# cdu.net
KiCad netlist of a schematic drawn in EAGLE
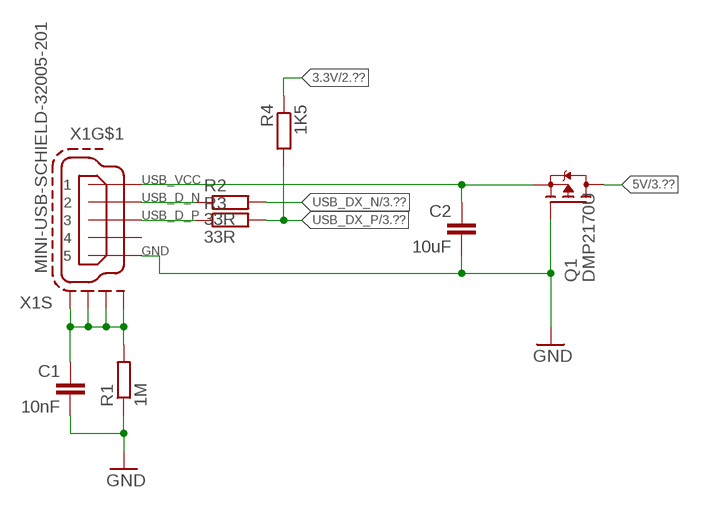
[diagram p0: schematic, sheet 1]
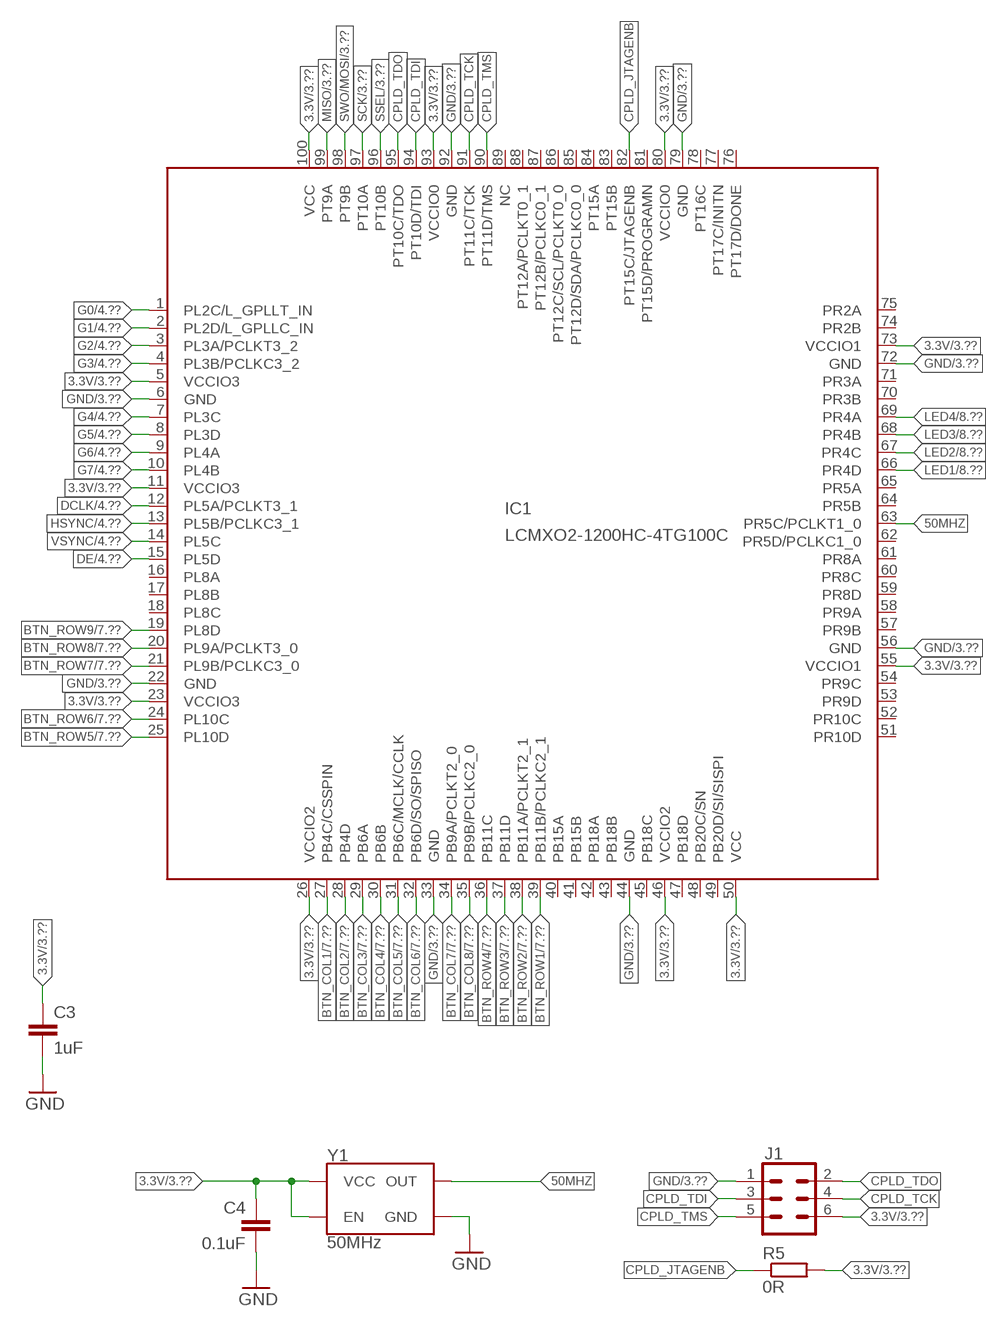
[diagram p1: schematic, sheet 2]
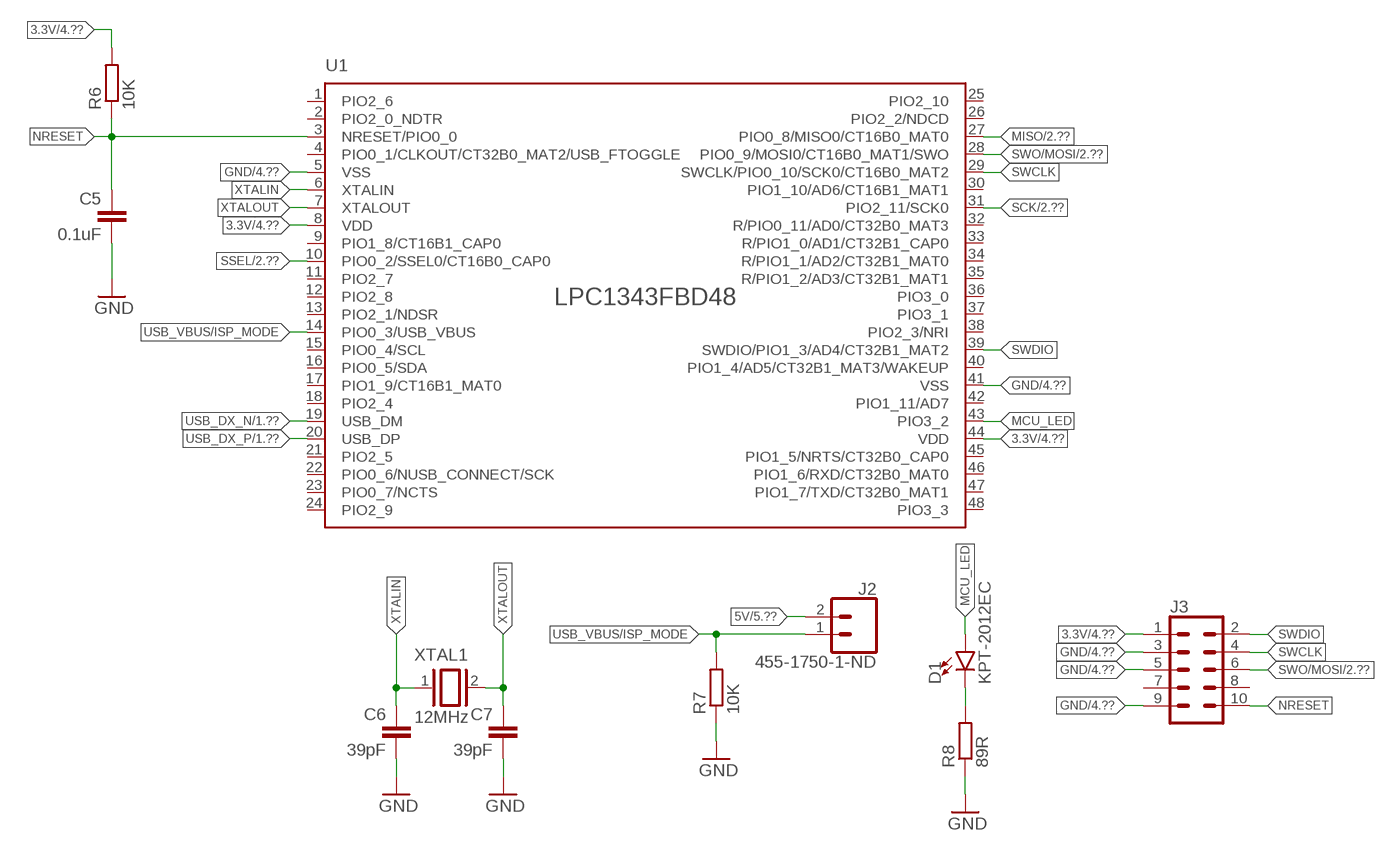
[diagram p2: schematic, sheet 3]
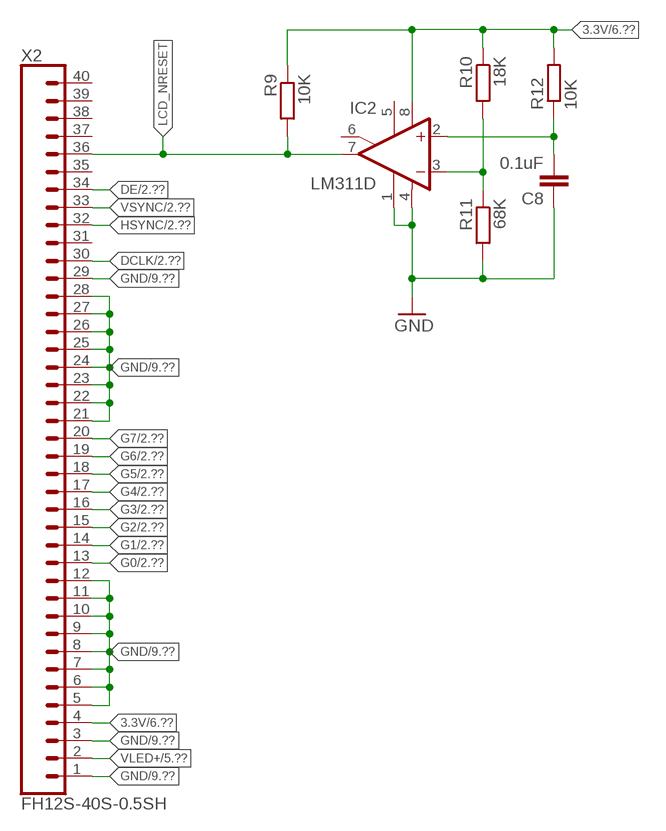
[diagram p3: schematic, sheet 4]
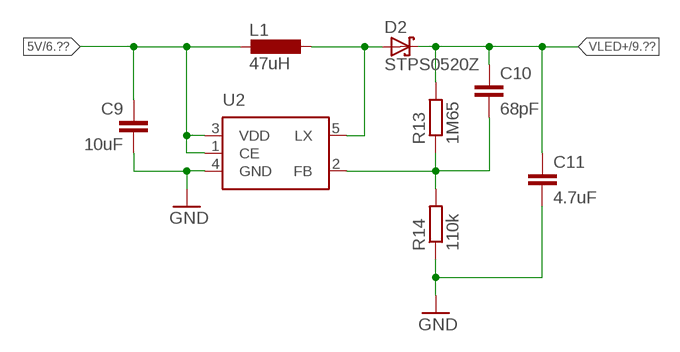
[diagram p4: schematic, sheet 5]
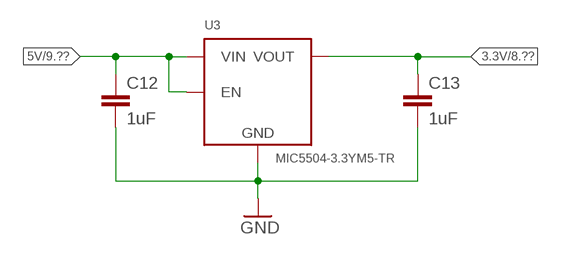
[diagram p5: schematic, sheet 6]
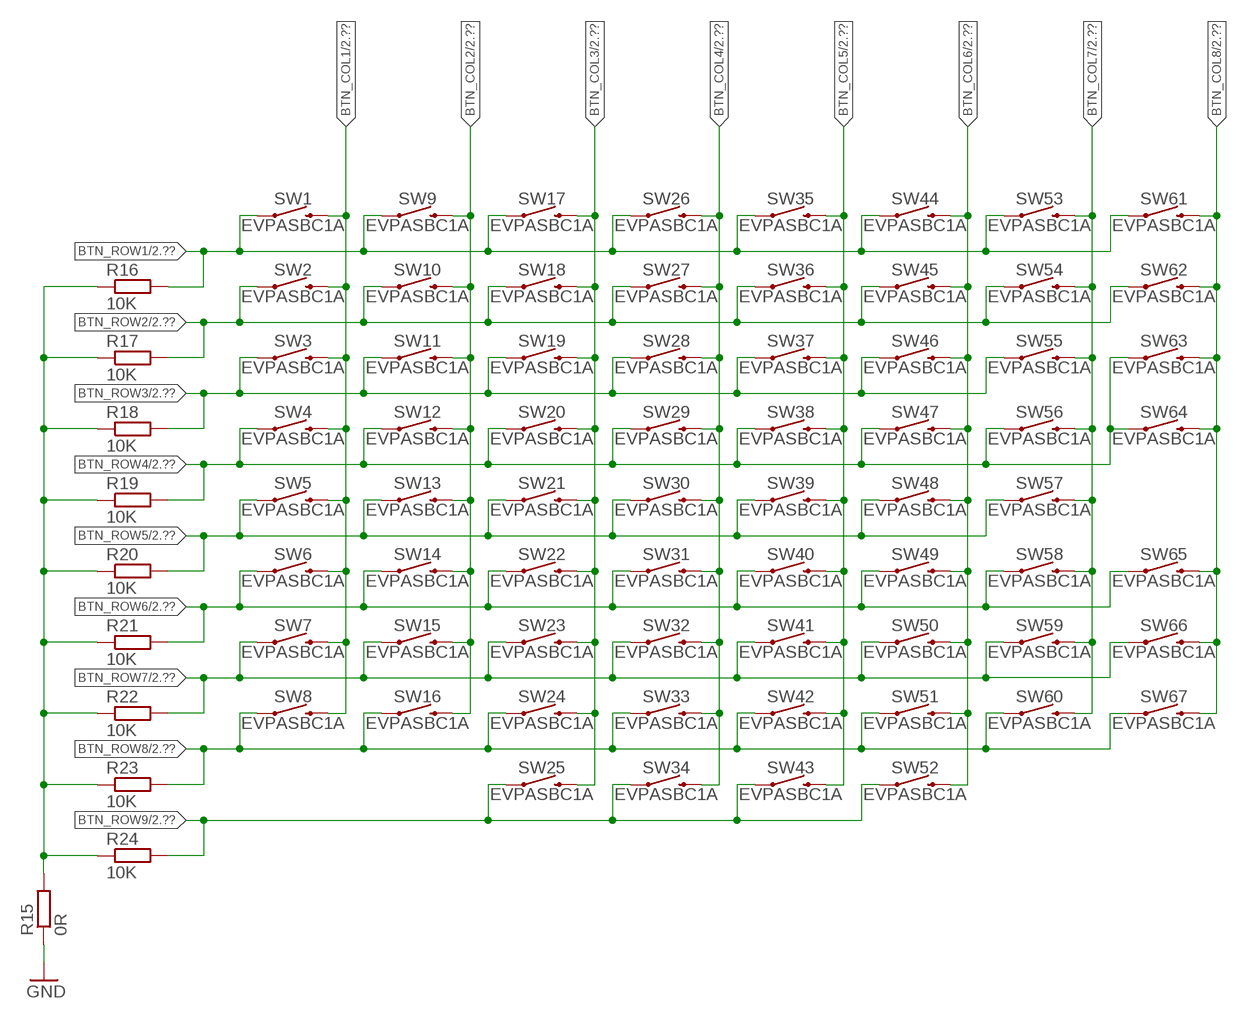
[diagram p6: schematic, sheet 7]
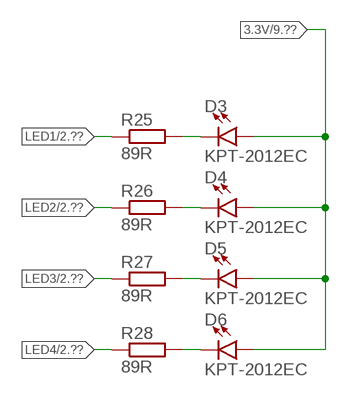
[diagram p7: schematic, sheet 8]
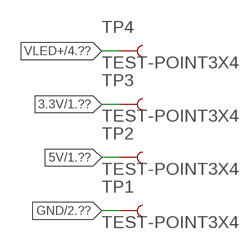
[diagram p8: schematic, sheet 9]

(export (version "E")
  (design (tool "Eeschema 10.0.6"))
  (components
    (comp (ref "TP1")
      (value "TEST-POINT3X4")
      (footprint "eagle-import:PAD.03X.04")
      (libsource (lib "eagle-import") (part "TEST-POINT3X4"))
    )
    (comp (ref "TP2")
      (value "TEST-POINT3X4")
      (footprint "eagle-import:PAD.03X.04")
      (libsource (lib "eagle-import") (part "TEST-POINT3X4"))
    )
    (comp (ref "TP3")
      (value "TEST-POINT3X4")
      (footprint "eagle-import:PAD.03X.04")
      (libsource (lib "eagle-import") (part "TEST-POINT3X4"))
    )
    (comp (ref "TP4")
      (value "TEST-POINT3X4")
      (footprint "eagle-import:PAD.03X.04")
      (libsource (lib "eagle-import") (part "TEST-POINT3X4"))
    )
    (comp (ref "C3")
      (value "1uF")
      (footprint "eagle-import:C0603")
      (libsource (lib "eagle-import") (part "resistor_348_C-EUC0603"))
    )
    (comp (ref "C4")
      (value "0.1uF")
      (footprint "eagle-import:C0603")
      (libsource (lib "eagle-import") (part "resistor_348_C-EUC0603"))
    )
    (comp (ref "IC1")
      (value "LCMXO2-1200HC-4TG100C")
      (footprint "eagle-import:TQFP100")
      (libsource (lib "eagle-import") (part "LCMXO2-1200HC-4TG100C"))
    )
    (comp (ref "J1")
      (value "CONN_03X2FEMALE_SMD")
      (footprint "eagle-import:2X3_SMD")
      (libsource (lib "eagle-import") (part "CONN_03X2FEMALE_SMD"))
    )
    (comp (ref "R5")
      (value "0R")
      (footprint "eagle-import:R0603")
      (libsource (lib "eagle-import") (part "resistor_348_R-EU_R0603"))
    )
    (comp (ref "Y1")
      (value "50MHz")
      (footprint "eagle-import:CFPS-73")
      (libsource (lib "eagle-import") (part "LFSPXO019987"))
    )
    (comp (ref "C5")
      (value "0.1uF")
      (footprint "eagle-import:C0603")
      (libsource (lib "eagle-import") (part "resistor_348_C-EUC0603"))
    )
    (comp (ref "C6")
      (value "39pF")
      (footprint "eagle-import:C0603")
      (libsource (lib "eagle-import") (part "resistor_348_C-EUC0603"))
    )
    (comp (ref "C7")
      (value "39pF")
      (footprint "eagle-import:C0603")
      (libsource (lib "eagle-import") (part "resistor_348_C-EUC0603"))
    )
    (comp (ref "D1")
      (value "KPT-2012EC")
      (footprint "eagle-import:KPT-2012EC")
      (libsource (lib "eagle-import") (part "KPT-2012EC"))
    )
    (comp (ref "J2")
      (value "455-1750-1-ND")
      (footprint "eagle-import:1X02_SMD")
      (libsource (lib "eagle-import") (part "CONN_02SMD"))
    )
    (comp (ref "J3")
      (value "CONN_05X2SMD_12.7")
      (footprint "eagle-import:2X5_SMD_1.27MM")
      (libsource (lib "eagle-import") (part "CONN_05X2SMD_12.7"))
    )
    (comp (ref "R6")
      (value "10K")
      (footprint "eagle-import:R0603")
      (libsource (lib "eagle-import") (part "resistor_348_R-EU_R0603"))
    )
    (comp (ref "R7")
      (value "10K")
      (footprint "eagle-import:R0603")
      (libsource (lib "eagle-import") (part "resistor_348_R-EU_R0603"))
    )
    (comp (ref "R8")
      (value "89R")
      (footprint "eagle-import:R0603")
      (libsource (lib "eagle-import") (part "resistor_348_R-EU_R0603"))
    )
    (comp (ref "U1")
      (value "LPC1343FBD48")
      (footprint "eagle-import:LQFP-48")
      (libsource (lib "eagle-import") (part "LPC1343FBD48"))
    )
    (comp (ref "XTAL1")
      (value "12MHz")
      (footprint "eagle-import:CAA-12.000-18-3050-X")
      (libsource (lib "eagle-import") (part "CRYSTAL"))
    )
    (comp (ref "C9")
      (value "10uF")
      (footprint "eagle-import:C0805K")
      (libsource (lib "eagle-import") (part "resistor_348_C-EUC0805K"))
    )
    (comp (ref "C10")
      (value "68pF")
      (footprint "eagle-import:C0603")
      (libsource (lib "eagle-import") (part "resistor_348_C-EUC0603"))
    )
    (comp (ref "C11")
      (value "4.7uF")
      (footprint "eagle-import:C0603")
      (libsource (lib "eagle-import") (part "resistor_348_C-EUC0603"))
    )
    (comp (ref "D2")
      (value "STPS0520Z")
      (footprint "eagle-import:SOD123")
      (libsource (lib "eagle-import") (part "STPS0520Z"))
    )
    (comp (ref "L1")
      (value "47uH")
      (footprint "eagle-import:TYS4018470M-10")
      (libsource (lib "eagle-import") (part "TYS4018470M-10"))
    )
    (comp (ref "R13")
      (value "1M65")
      (footprint "eagle-import:R0603")
      (libsource (lib "eagle-import") (part "resistor_348_R-EU_R0603"))
    )
    (comp (ref "R14")
      (value "110k")
      (footprint "eagle-import:R0603")
      (libsource (lib "eagle-import") (part "resistor_348_R-EU_R0603"))
    )
    (comp (ref "U2")
      (value "NCP1406")
      (footprint "eagle-import:TSOP-5")
      (libsource (lib "eagle-import") (part "NCP1406"))
    )
    (comp (ref "C1")
      (value "10nF")
      (footprint "eagle-import:C0603")
      (libsource (lib "eagle-import") (part "resistor_348_C-EUC0603"))
    )
    (comp (ref "C2")
      (value "10uF")
      (footprint "eagle-import:C0805K")
      (libsource (lib "eagle-import") (part "resistor_348_C-EUC0805K"))
    )
    (comp (ref "Q1")
      (value "DMP2170U")
      (footprint "eagle-import:SOT23")
      (libsource (lib "eagle-import") (part "DMP2170U"))
    )
    (comp (ref "R1")
      (value "1M")
      (footprint "eagle-import:R0603")
      (libsource (lib "eagle-import") (part "resistor_348_R-EU_R0603"))
    )
    (comp (ref "R2")
      (value "33R")
      (footprint "eagle-import:R0603")
      (libsource (lib "eagle-import") (part "resistor_348_R-EU_R0603"))
    )
    (comp (ref "R3")
      (value "33R")
      (footprint "eagle-import:R0603")
      (libsource (lib "eagle-import") (part "resistor_348_R-EU_R0603"))
    )
    (comp (ref "R4")
      (value "1K5")
      (footprint "eagle-import:R0603")
      (libsource (lib "eagle-import") (part "resistor_348_R-EU_R0603"))
    )
    (comp (ref "X1")
      (value "MINI-USB-SCHIELD-32005-201")
      (footprint "eagle-import:32005-201")
      (libsource (lib "eagle-import") (part "MINI-USB-SCHIELD-32005-201"))
    )
    (comp (ref "C8")
      (value "0.1uF")
      (footprint "eagle-import:C0603")
      (libsource (lib "eagle-import") (part "C-EUC0603"))
    )
    (comp (ref "IC2")
      (value "LM311D")
      (footprint "eagle-import:SO08")
      (libsource (lib "eagle-import") (part "LM311D"))
    )
    (comp (ref "R9")
      (value "10K")
      (footprint "eagle-import:R0603")
      (libsource (lib "eagle-import") (part "R-EU_R0603"))
    )
    (comp (ref "R10")
      (value "18K")
      (footprint "eagle-import:R0603")
      (libsource (lib "eagle-import") (part "R-EU_R0603"))
    )
    (comp (ref "R11")
      (value "68K")
      (footprint "eagle-import:R0603")
      (libsource (lib "eagle-import") (part "R-EU_R0603"))
    )
    (comp (ref "R12")
      (value "10K")
      (footprint "eagle-import:R0603")
      (libsource (lib "eagle-import") (part "R-EU_R0603"))
    )
    (comp (ref "X2")
      (value "FH12S-40S-0.5SH")
      (footprint "eagle-import:FH12S-40S-0.5SH")
      (libsource (lib "eagle-import") (part "FH12S-40S-0.5SH"))
    )
    (comp (ref "D3")
      (value "KPT-2012EC")
      (footprint "eagle-import:KPT-2012EC")
      (libsource (lib "eagle-import") (part "KPT-2012EC"))
    )
    (comp (ref "D4")
      (value "KPT-2012EC")
      (footprint "eagle-import:KPT-2012EC")
      (libsource (lib "eagle-import") (part "KPT-2012EC"))
    )
    (comp (ref "D5")
      (value "KPT-2012EC")
      (footprint "eagle-import:KPT-2012EC")
      (libsource (lib "eagle-import") (part "KPT-2012EC"))
    )
    (comp (ref "D6")
      (value "KPT-2012EC")
      (footprint "eagle-import:KPT-2012EC")
      (libsource (lib "eagle-import") (part "KPT-2012EC"))
    )
    (comp (ref "R25")
      (value "89R")
      (footprint "eagle-import:R0603")
      (libsource (lib "eagle-import") (part "resistor_348_R-EU_R0603"))
    )
    (comp (ref "R26")
      (value "89R")
      (footprint "eagle-import:R0603")
      (libsource (lib "eagle-import") (part "resistor_348_R-EU_R0603"))
    )
    (comp (ref "R27")
      (value "89R")
      (footprint "eagle-import:R0603")
      (libsource (lib "eagle-import") (part "resistor_348_R-EU_R0603"))
    )
    (comp (ref "R28")
      (value "89R")
      (footprint "eagle-import:R0603")
      (libsource (lib "eagle-import") (part "resistor_348_R-EU_R0603"))
    )
    (comp (ref "R15")
      (value "0R")
      (footprint "eagle-import:R0603")
      (libsource (lib "eagle-import") (part "resistor_348_R-EU_R0603"))
    )
    (comp (ref "R16")
      (value "10K")
      (footprint "eagle-import:R0603")
      (libsource (lib "eagle-import") (part "resistor_348_R-EU_R0603"))
    )
    (comp (ref "R17")
      (value "10K")
      (footprint "eagle-import:R0603")
      (libsource (lib "eagle-import") (part "resistor_348_R-EU_R0603"))
    )
    (comp (ref "R18")
      (value "10K")
      (footprint "eagle-import:R0603")
      (libsource (lib "eagle-import") (part "resistor_348_R-EU_R0603"))
    )
    (comp (ref "R19")
      (value "10K")
      (footprint "eagle-import:R0603")
      (libsource (lib "eagle-import") (part "resistor_348_R-EU_R0603"))
    )
    (comp (ref "R20")
      (value "10K")
      (footprint "eagle-import:R0603")
      (libsource (lib "eagle-import") (part "resistor_348_R-EU_R0603"))
    )
    (comp (ref "R21")
      (value "10K")
      (footprint "eagle-import:R0603")
      (libsource (lib "eagle-import") (part "resistor_348_R-EU_R0603"))
    )
    (comp (ref "R22")
      (value "10K")
      (footprint "eagle-import:R0603")
      (libsource (lib "eagle-import") (part "resistor_348_R-EU_R0603"))
    )
    (comp (ref "R23")
      (value "10K")
      (footprint "eagle-import:R0603")
      (libsource (lib "eagle-import") (part "resistor_348_R-EU_R0603"))
    )
    (comp (ref "R24")
      (value "10K")
      (footprint "eagle-import:R0603")
      (libsource (lib "eagle-import") (part "resistor_348_R-EU_R0603"))
    )
    (comp (ref "SW1")
      (value "EVPASBC1A")
      (footprint "eagle-import:EVPASBC1A")
      (libsource (lib "eagle-import") (part "EVPASBC1A"))
    )
    (comp (ref "SW2")
      (value "EVPASBC1A")
      (footprint "eagle-import:EVPASBC1A")
      (libsource (lib "eagle-import") (part "EVPASBC1A"))
    )
    (comp (ref "SW3")
      (value "EVPASBC1A")
      (footprint "eagle-import:EVPASBC1A")
      (libsource (lib "eagle-import") (part "EVPASBC1A"))
    )
    (comp (ref "SW4")
      (value "EVPASBC1A")
      (footprint "eagle-import:EVPASBC1A")
      (libsource (lib "eagle-import") (part "EVPASBC1A"))
    )
    (comp (ref "SW5")
      (value "EVPASBC1A")
      (footprint "eagle-import:EVPASBC1A")
      (libsource (lib "eagle-import") (part "EVPASBC1A"))
    )
    (comp (ref "SW6")
      (value "EVPASBC1A")
      (footprint "eagle-import:EVPASBC1A")
      (libsource (lib "eagle-import") (part "EVPASBC1A"))
    )
    (comp (ref "SW7")
      (value "EVPASBC1A")
      (footprint "eagle-import:EVPASBC1A")
      (libsource (lib "eagle-import") (part "EVPASBC1A"))
    )
    (comp (ref "SW8")
      (value "EVPASBC1A")
      (footprint "eagle-import:EVPASBC1A")
      (libsource (lib "eagle-import") (part "EVPASBC1A"))
    )
    (comp (ref "SW9")
      (value "EVPASBC1A")
      (footprint "eagle-import:EVPASBC1A")
      (libsource (lib "eagle-import") (part "EVPASBC1A"))
    )
    (comp (ref "SW10")
      (value "EVPASBC1A")
      (footprint "eagle-import:EVPASBC1A")
      (libsource (lib "eagle-import") (part "EVPASBC1A"))
    )
    (comp (ref "SW11")
      (value "EVPASBC1A")
      (footprint "eagle-import:EVPASBC1A")
      (libsource (lib "eagle-import") (part "EVPASBC1A"))
    )
    (comp (ref "SW12")
      (value "EVPASBC1A")
      (footprint "eagle-import:EVPASBC1A")
      (libsource (lib "eagle-import") (part "EVPASBC1A"))
    )
    (comp (ref "SW13")
      (value "EVPASBC1A")
      (footprint "eagle-import:EVPASBC1A")
      (libsource (lib "eagle-import") (part "EVPASBC1A"))
    )
    (comp (ref "SW14")
      (value "EVPASBC1A")
      (footprint "eagle-import:EVPASBC1A")
      (libsource (lib "eagle-import") (part "EVPASBC1A"))
    )
    (comp (ref "SW15")
      (value "EVPASBC1A")
      (footprint "eagle-import:EVPASBC1A")
      (libsource (lib "eagle-import") (part "EVPASBC1A"))
    )
    (comp (ref "SW16")
      (value "EVPASBC1A")
      (footprint "eagle-import:EVPASBC1A")
      (libsource (lib "eagle-import") (part "EVPASBC1A"))
    )
    (comp (ref "SW17")
      (value "EVPASBC1A")
      (footprint "eagle-import:EVPASBC1A")
      (libsource (lib "eagle-import") (part "EVPASBC1A"))
    )
    (comp (ref "SW18")
      (value "EVPASBC1A")
      (footprint "eagle-import:EVPASBC1A")
      (libsource (lib "eagle-import") (part "EVPASBC1A"))
    )
    (comp (ref "SW19")
      (value "EVPASBC1A")
      (footprint "eagle-import:EVPASBC1A")
      (libsource (lib "eagle-import") (part "EVPASBC1A"))
    )
    (comp (ref "SW20")
      (value "EVPASBC1A")
      (footprint "eagle-import:EVPASBC1A")
      (libsource (lib "eagle-import") (part "EVPASBC1A"))
    )
    (comp (ref "SW21")
      (value "EVPASBC1A")
      (footprint "eagle-import:EVPASBC1A")
      (libsource (lib "eagle-import") (part "EVPASBC1A"))
    )
    (comp (ref "SW22")
      (value "EVPASBC1A")
      (footprint "eagle-import:EVPASBC1A")
      (libsource (lib "eagle-import") (part "EVPASBC1A"))
    )
    (comp (ref "SW23")
      (value "EVPASBC1A")
      (footprint "eagle-import:EVPASBC1A")
      (libsource (lib "eagle-import") (part "EVPASBC1A"))
    )
    (comp (ref "SW24")
      (value "EVPASBC1A")
      (footprint "eagle-import:EVPASBC1A")
      (libsource (lib "eagle-import") (part "EVPASBC1A"))
    )
    (comp (ref "SW25")
      (value "EVPASBC1A")
      (footprint "eagle-import:EVPASBC1A")
      (libsource (lib "eagle-import") (part "EVPASBC1A"))
    )
    (comp (ref "SW26")
      (value "EVPASBC1A")
      (footprint "eagle-import:EVPASBC1A")
      (libsource (lib "eagle-import") (part "EVPASBC1A"))
    )
    (comp (ref "SW27")
      (value "EVPASBC1A")
      (footprint "eagle-import:EVPASBC1A")
      (libsource (lib "eagle-import") (part "EVPASBC1A"))
    )
    (comp (ref "SW28")
      (value "EVPASBC1A")
      (footprint "eagle-import:EVPASBC1A")
      (libsource (lib "eagle-import") (part "EVPASBC1A"))
    )
    (comp (ref "SW29")
      (value "EVPASBC1A")
      (footprint "eagle-import:EVPASBC1A")
      (libsource (lib "eagle-import") (part "EVPASBC1A"))
    )
    (comp (ref "SW30")
      (value "EVPASBC1A")
      (footprint "eagle-import:EVPASBC1A")
      (libsource (lib "eagle-import") (part "EVPASBC1A"))
    )
    (comp (ref "SW31")
      (value "EVPASBC1A")
      (footprint "eagle-import:EVPASBC1A")
      (libsource (lib "eagle-import") (part "EVPASBC1A"))
    )
    (comp (ref "SW32")
      (value "EVPASBC1A")
      (footprint "eagle-import:EVPASBC1A")
      (libsource (lib "eagle-import") (part "EVPASBC1A"))
    )
    (comp (ref "SW33")
      (value "EVPASBC1A")
      (footprint "eagle-import:EVPASBC1A")
      (libsource (lib "eagle-import") (part "EVPASBC1A"))
    )
    (comp (ref "SW34")
      (value "EVPASBC1A")
      (footprint "eagle-import:EVPASBC1A")
      (libsource (lib "eagle-import") (part "EVPASBC1A"))
    )
    (comp (ref "SW35")
      (value "EVPASBC1A")
      (footprint "eagle-import:EVPASBC1A")
      (libsource (lib "eagle-import") (part "EVPASBC1A"))
    )
    (comp (ref "SW36")
      (value "EVPASBC1A")
      (footprint "eagle-import:EVPASBC1A")
      (libsource (lib "eagle-import") (part "EVPASBC1A"))
    )
    (comp (ref "SW37")
      (value "EVPASBC1A")
      (footprint "eagle-import:EVPASBC1A")
      (libsource (lib "eagle-import") (part "EVPASBC1A"))
    )
    (comp (ref "SW38")
      (value "EVPASBC1A")
      (footprint "eagle-import:EVPASBC1A")
      (libsource (lib "eagle-import") (part "EVPASBC1A"))
    )
    (comp (ref "SW39")
      (value "EVPASBC1A")
      (footprint "eagle-import:EVPASBC1A")
      (libsource (lib "eagle-import") (part "EVPASBC1A"))
    )
    (comp (ref "SW40")
      (value "EVPASBC1A")
      (footprint "eagle-import:EVPASBC1A")
      (libsource (lib "eagle-import") (part "EVPASBC1A"))
    )
    (comp (ref "SW41")
      (value "EVPASBC1A")
      (footprint "eagle-import:EVPASBC1A")
      (libsource (lib "eagle-import") (part "EVPASBC1A"))
    )
    (comp (ref "SW42")
      (value "EVPASBC1A")
      (footprint "eagle-import:EVPASBC1A")
      (libsource (lib "eagle-import") (part "EVPASBC1A"))
    )
    (comp (ref "SW43")
      (value "EVPASBC1A")
      (footprint "eagle-import:EVPASBC1A")
      (libsource (lib "eagle-import") (part "EVPASBC1A"))
    )
    (comp (ref "SW44")
      (value "EVPASBC1A")
      (footprint "eagle-import:EVPASBC1A")
      (libsource (lib "eagle-import") (part "EVPASBC1A"))
    )
    (comp (ref "SW45")
      (value "EVPASBC1A")
      (footprint "eagle-import:EVPASBC1A")
      (libsource (lib "eagle-import") (part "EVPASBC1A"))
    )
    (comp (ref "SW46")
      (value "EVPASBC1A")
      (footprint "eagle-import:EVPASBC1A")
      (libsource (lib "eagle-import") (part "EVPASBC1A"))
    )
    (comp (ref "SW47")
      (value "EVPASBC1A")
      (footprint "eagle-import:EVPASBC1A")
      (libsource (lib "eagle-import") (part "EVPASBC1A"))
    )
    (comp (ref "SW48")
      (value "EVPASBC1A")
      (footprint "eagle-import:EVPASBC1A")
      (libsource (lib "eagle-import") (part "EVPASBC1A"))
    )
    (comp (ref "SW49")
      (value "EVPASBC1A")
      (footprint "eagle-import:EVPASBC1A")
      (libsource (lib "eagle-import") (part "EVPASBC1A"))
    )
    (comp (ref "SW50")
      (value "EVPASBC1A")
      (footprint "eagle-import:EVPASBC1A")
      (libsource (lib "eagle-import") (part "EVPASBC1A"))
    )
    (comp (ref "SW51")
      (value "EVPASBC1A")
      (footprint "eagle-import:EVPASBC1A")
      (libsource (lib "eagle-import") (part "EVPASBC1A"))
    )
    (comp (ref "SW52")
      (value "EVPASBC1A")
      (footprint "eagle-import:EVPASBC1A")
      (libsource (lib "eagle-import") (part "EVPASBC1A"))
    )
    (comp (ref "SW53")
      (value "EVPASBC1A")
      (footprint "eagle-import:EVPASBC1A")
      (libsource (lib "eagle-import") (part "EVPASBC1A"))
    )
    (comp (ref "SW54")
      (value "EVPASBC1A")
      (footprint "eagle-import:EVPASBC1A")
      (libsource (lib "eagle-import") (part "EVPASBC1A"))
    )
    (comp (ref "SW55")
      (value "EVPASBC1A")
      (footprint "eagle-import:EVPASBC1A")
      (libsource (lib "eagle-import") (part "EVPASBC1A"))
    )
    (comp (ref "SW56")
      (value "EVPASBC1A")
      (footprint "eagle-import:EVPASBC1A")
      (libsource (lib "eagle-import") (part "EVPASBC1A"))
    )
    (comp (ref "SW57")
      (value "EVPASBC1A")
      (footprint "eagle-import:EVPASBC1A")
      (libsource (lib "eagle-import") (part "EVPASBC1A"))
    )
    (comp (ref "SW58")
      (value "EVPASBC1A")
      (footprint "eagle-import:EVPASBC1A")
      (libsource (lib "eagle-import") (part "EVPASBC1A"))
    )
    (comp (ref "SW59")
      (value "EVPASBC1A")
      (footprint "eagle-import:EVPASBC1A")
      (libsource (lib "eagle-import") (part "EVPASBC1A"))
    )
    (comp (ref "SW60")
      (value "EVPASBC1A")
      (footprint "eagle-import:EVPASBC1A")
      (libsource (lib "eagle-import") (part "EVPASBC1A"))
    )
    (comp (ref "SW61")
      (value "EVPASBC1A")
      (footprint "eagle-import:EVPASBC1A")
      (libsource (lib "eagle-import") (part "EVPASBC1A"))
    )
    (comp (ref "SW62")
      (value "EVPASBC1A")
      (footprint "eagle-import:EVPASBC1A")
      (libsource (lib "eagle-import") (part "EVPASBC1A"))
    )
    (comp (ref "SW63")
      (value "EVPASBC1A")
      (footprint "eagle-import:EVPASBC1A")
      (libsource (lib "eagle-import") (part "EVPASBC1A"))
    )
    (comp (ref "SW64")
      (value "EVPASBC1A")
      (footprint "eagle-import:EVPASBC1A")
      (libsource (lib "eagle-import") (part "EVPASBC1A"))
    )
    (comp (ref "SW65")
      (value "EVPASBC1A")
      (footprint "eagle-import:EVPASBC1A")
      (libsource (lib "eagle-import") (part "EVPASBC1A"))
    )
    (comp (ref "SW66")
      (value "EVPASBC1A")
      (footprint "eagle-import:EVPASBC1A")
      (libsource (lib "eagle-import") (part "EVPASBC1A"))
    )
    (comp (ref "SW67")
      (value "EVPASBC1A")
      (footprint "eagle-import:EVPASBC1A")
      (libsource (lib "eagle-import") (part "EVPASBC1A"))
    )
    (comp (ref "C12")
      (value "1uF")
      (footprint "eagle-import:C0603")
      (libsource (lib "eagle-import") (part "resistor_348_C-EUC0603"))
    )
    (comp (ref "C13")
      (value "1uF")
      (footprint "eagle-import:C0603")
      (libsource (lib "eagle-import") (part "resistor_348_C-EUC0603"))
    )
    (comp (ref "U3")
      (value "MIC5504-3.3YM5-TR")
      (footprint "eagle-import:SOT23-5")
      (fields (field (name "SPICEPREFIX") "E"))
      (libsource (lib "eagle-import") (part "MIC5504-TR-3.3YM5"))
    )
  )
  (nets
    (net (code "1") (name "3.3V") (class "Default")
      (node (ref "C13") (pin "1") (pinfunction "1_1") (pintype "passive"))
      (node (ref "C3") (pin "1") (pinfunction "1_1") (pintype "passive"))
      (node (ref "C4") (pin "1") (pinfunction "1_1") (pintype "passive"))
      (node (ref "D3") (pin "A") (pinfunction "A_A") (pintype "passive"))
      (node (ref "D4") (pin "A") (pinfunction "A_A") (pintype "passive"))
      (node (ref "D5") (pin "A") (pinfunction "A_A") (pintype "passive"))
      (node (ref "D6") (pin "A") (pinfunction "A_A") (pintype "passive"))
      (node (ref "IC1") (pin "100") (pinfunction "VCC_100") (pintype "power_in"))
      (node (ref "IC1") (pin "11") (pinfunction "VCCIO3_11") (pintype "power_in"))
      (node (ref "IC1") (pin "23") (pinfunction "VCCIO3_23") (pintype "power_in"))
      (node (ref "IC1") (pin "26") (pinfunction "VCCIO2_26") (pintype "power_in"))
      (node (ref "IC1") (pin "46") (pinfunction "VCCIO2_46") (pintype "power_in"))
      (node (ref "IC1") (pin "5") (pinfunction "VCCIO3_5") (pintype "power_in"))
      (node (ref "IC1") (pin "50") (pinfunction "VCC_50") (pintype "power_in"))
      (node (ref "IC1") (pin "55") (pinfunction "VCCIO1_55") (pintype "power_in"))
      (node (ref "IC1") (pin "73") (pinfunction "VCCIO1_73") (pintype "power_in"))
      (node (ref "IC1") (pin "80") (pinfunction "VCCIO0_80") (pintype "power_in"))
      (node (ref "IC1") (pin "93") (pinfunction "VCCIO0_93") (pintype "power_in"))
      (node (ref "IC2") (pin "8") (pinfunction "V+_8") (pintype "power_in"))
      (node (ref "J1") (pin "6") (pinfunction "6_6") (pintype "bidirectional"))
      (node (ref "J3") (pin "1") (pinfunction "1_1") (pintype "passive"))
      (node (ref "R10") (pin "1") (pinfunction "1_1") (pintype "passive"))
      (node (ref "R12") (pin "2") (pinfunction "2_2") (pintype "passive"))
      (node (ref "R4") (pin "1") (pinfunction "1_1") (pintype "passive"))
      (node (ref "R5") (pin "2") (pinfunction "2_2") (pintype "passive"))
      (node (ref "R6") (pin "2") (pinfunction "2_2") (pintype "passive"))
      (node (ref "R9") (pin "1") (pinfunction "1_1") (pintype "passive"))
      (node (ref "TP3") (pin "P$1") (pinfunction "1_P$1") (pintype "bidirectional"))
      (node (ref "U1") (pin "44") (pinfunction "VDD_44") (pintype "bidirectional"))
      (node (ref "U1") (pin "8") (pinfunction "VDD_8") (pintype "bidirectional"))
      (node (ref "U3") (pin "5") (pinfunction "VOUT_5") (pintype "power_in"))
      (node (ref "X2") (pin "4") (pinfunction "4_4") (pintype "passive"))
      (node (ref "Y1") (pin "1") (pinfunction "EN_1") (pintype "bidirectional"))
      (node (ref "Y1") (pin "4") (pinfunction "VCC_4") (pintype "bidirectional"))
    )
    (net (code "2") (name "5V") (class "Default")
      (node (ref "C12") (pin "1") (pinfunction "1_1") (pintype "passive"))
      (node (ref "C9") (pin "1") (pinfunction "1_1") (pintype "passive"))
      (node (ref "J2") (pin "2") (pinfunction "2_2") (pintype "passive"))
      (node (ref "L1") (pin "2") (pinfunction "2_2") (pintype "passive"))
      (node (ref "Q1") (pin "3") (pinfunction "D_3") (pintype "passive"))
      (node (ref "TP2") (pin "P$1") (pinfunction "1_P$1") (pintype "bidirectional"))
      (node (ref "U2") (pin "1") (pinfunction "CE_1") (pintype "bidirectional"))
      (node (ref "U2") (pin "3") (pinfunction "VDD_3") (pintype "bidirectional"))
      (node (ref "U3") (pin "1") (pinfunction "VIN_1") (pintype "power_in"))
      (node (ref "U3") (pin "3") (pinfunction "EN_3") (pintype "input"))
    )
    (net (code "3") (name "50MHZ") (class "Default")
      (node (ref "IC1") (pin "63") (pinfunction "PR5C/PCLKT1_0_63") (pintype "bidirectional"))
      (node (ref "Y1") (pin "3") (pinfunction "OUT_3") (pintype "bidirectional"))
    )
    (net (code "4") (name "BTN_COL1") (class "Default")
      (node (ref "IC1") (pin "27") (pinfunction "PB4C/CSSPIN_27") (pintype "bidirectional"))
      (node (ref "SW1") (pin "P$2") (pinfunction "2_P$2") (pintype "passive"))
      (node (ref "SW2") (pin "P$2") (pinfunction "2_P$2") (pintype "passive"))
      (node (ref "SW3") (pin "P$2") (pinfunction "2_P$2") (pintype "passive"))
      (node (ref "SW4") (pin "P$2") (pinfunction "2_P$2") (pintype "passive"))
      (node (ref "SW5") (pin "P$2") (pinfunction "2_P$2") (pintype "passive"))
      (node (ref "SW6") (pin "P$2") (pinfunction "2_P$2") (pintype "passive"))
      (node (ref "SW7") (pin "P$2") (pinfunction "2_P$2") (pintype "passive"))
      (node (ref "SW8") (pin "P$2") (pinfunction "2_P$2") (pintype "passive"))
    )
    (net (code "5") (name "BTN_COL2") (class "Default")
      (node (ref "IC1") (pin "28") (pinfunction "PB4D_28") (pintype "bidirectional"))
      (node (ref "SW10") (pin "P$2") (pinfunction "2_P$2") (pintype "passive"))
      (node (ref "SW11") (pin "P$2") (pinfunction "2_P$2") (pintype "passive"))
      (node (ref "SW12") (pin "P$2") (pinfunction "2_P$2") (pintype "passive"))
      (node (ref "SW13") (pin "P$2") (pinfunction "2_P$2") (pintype "passive"))
      (node (ref "SW14") (pin "P$2") (pinfunction "2_P$2") (pintype "passive"))
      (node (ref "SW15") (pin "P$2") (pinfunction "2_P$2") (pintype "passive"))
      (node (ref "SW16") (pin "P$2") (pinfunction "2_P$2") (pintype "passive"))
      (node (ref "SW9") (pin "P$2") (pinfunction "2_P$2") (pintype "passive"))
    )
    (net (code "6") (name "BTN_COL3") (class "Default")
      (node (ref "IC1") (pin "29") (pinfunction "PB6A_29") (pintype "bidirectional"))
      (node (ref "SW17") (pin "P$2") (pinfunction "2_P$2") (pintype "passive"))
      (node (ref "SW18") (pin "P$2") (pinfunction "2_P$2") (pintype "passive"))
      (node (ref "SW19") (pin "P$2") (pinfunction "2_P$2") (pintype "passive"))
      (node (ref "SW20") (pin "P$2") (pinfunction "2_P$2") (pintype "passive"))
      (node (ref "SW21") (pin "P$2") (pinfunction "2_P$2") (pintype "passive"))
      (node (ref "SW22") (pin "P$2") (pinfunction "2_P$2") (pintype "passive"))
      (node (ref "SW23") (pin "P$2") (pinfunction "2_P$2") (pintype "passive"))
      (node (ref "SW24") (pin "P$2") (pinfunction "2_P$2") (pintype "passive"))
      (node (ref "SW25") (pin "P$2") (pinfunction "2_P$2") (pintype "passive"))
    )
    (net (code "7") (name "BTN_COL4") (class "Default")
      (node (ref "IC1") (pin "30") (pinfunction "PB6B_30") (pintype "bidirectional"))
      (node (ref "SW26") (pin "P$2") (pinfunction "2_P$2") (pintype "passive"))
      (node (ref "SW27") (pin "P$2") (pinfunction "2_P$2") (pintype "passive"))
      (node (ref "SW28") (pin "P$2") (pinfunction "2_P$2") (pintype "passive"))
      (node (ref "SW29") (pin "P$2") (pinfunction "2_P$2") (pintype "passive"))
      (node (ref "SW30") (pin "P$2") (pinfunction "2_P$2") (pintype "passive"))
      (node (ref "SW31") (pin "P$2") (pinfunction "2_P$2") (pintype "passive"))
      (node (ref "SW32") (pin "P$2") (pinfunction "2_P$2") (pintype "passive"))
      (node (ref "SW33") (pin "P$2") (pinfunction "2_P$2") (pintype "passive"))
      (node (ref "SW34") (pin "P$2") (pinfunction "2_P$2") (pintype "passive"))
    )
    (net (code "8") (name "BTN_COL5") (class "Default")
      (node (ref "IC1") (pin "31") (pinfunction "PB6C/MCLK/CCLK_31") (pintype "bidirectional"))
      (node (ref "SW35") (pin "P$2") (pinfunction "2_P$2") (pintype "passive"))
      (node (ref "SW36") (pin "P$2") (pinfunction "2_P$2") (pintype "passive"))
      (node (ref "SW37") (pin "P$2") (pinfunction "2_P$2") (pintype "passive"))
      (node (ref "SW38") (pin "P$2") (pinfunction "2_P$2") (pintype "passive"))
      (node (ref "SW39") (pin "P$2") (pinfunction "2_P$2") (pintype "passive"))
      (node (ref "SW40") (pin "P$2") (pinfunction "2_P$2") (pintype "passive"))
      (node (ref "SW41") (pin "P$2") (pinfunction "2_P$2") (pintype "passive"))
      (node (ref "SW42") (pin "P$2") (pinfunction "2_P$2") (pintype "passive"))
      (node (ref "SW43") (pin "P$2") (pinfunction "2_P$2") (pintype "passive"))
    )
    (net (code "9") (name "BTN_COL6") (class "Default")
      (node (ref "IC1") (pin "32") (pinfunction "PB6D/SO/SPISO_32") (pintype "bidirectional"))
      (node (ref "SW44") (pin "P$2") (pinfunction "2_P$2") (pintype "passive"))
      (node (ref "SW45") (pin "P$2") (pinfunction "2_P$2") (pintype "passive"))
      (node (ref "SW46") (pin "P$2") (pinfunction "2_P$2") (pintype "passive"))
      (node (ref "SW47") (pin "P$2") (pinfunction "2_P$2") (pintype "passive"))
      (node (ref "SW48") (pin "P$2") (pinfunction "2_P$2") (pintype "passive"))
      (node (ref "SW49") (pin "P$2") (pinfunction "2_P$2") (pintype "passive"))
      (node (ref "SW50") (pin "P$2") (pinfunction "2_P$2") (pintype "passive"))
      (node (ref "SW51") (pin "P$2") (pinfunction "2_P$2") (pintype "passive"))
      (node (ref "SW52") (pin "P$2") (pinfunction "2_P$2") (pintype "passive"))
    )
    (net (code "10") (name "BTN_COL7") (class "Default")
      (node (ref "IC1") (pin "34") (pinfunction "PB9A/PCLKT2_0_34") (pintype "bidirectional"))
      (node (ref "SW53") (pin "P$2") (pinfunction "2_P$2") (pintype "passive"))
      (node (ref "SW54") (pin "P$2") (pinfunction "2_P$2") (pintype "passive"))
      (node (ref "SW55") (pin "P$2") (pinfunction "2_P$2") (pintype "passive"))
      (node (ref "SW56") (pin "P$2") (pinfunction "2_P$2") (pintype "passive"))
      (node (ref "SW57") (pin "P$2") (pinfunction "2_P$2") (pintype "passive"))
      (node (ref "SW58") (pin "P$2") (pinfunction "2_P$2") (pintype "passive"))
      (node (ref "SW59") (pin "P$2") (pinfunction "2_P$2") (pintype "passive"))
      (node (ref "SW60") (pin "P$2") (pinfunction "2_P$2") (pintype "passive"))
    )
    (net (code "11") (name "BTN_COL8") (class "Default")
      (node (ref "IC1") (pin "35") (pinfunction "PB9B/PCLKC2_0_35") (pintype "bidirectional"))
      (node (ref "SW61") (pin "P$2") (pinfunction "2_P$2") (pintype "passive"))
      (node (ref "SW62") (pin "P$2") (pinfunction "2_P$2") (pintype "passive"))
      (node (ref "SW63") (pin "P$2") (pinfunction "2_P$2") (pintype "passive"))
      (node (ref "SW64") (pin "P$2") (pinfunction "2_P$2") (pintype "passive"))
      (node (ref "SW65") (pin "P$2") (pinfunction "2_P$2") (pintype "passive"))
      (node (ref "SW66") (pin "P$2") (pinfunction "2_P$2") (pintype "passive"))
      (node (ref "SW67") (pin "P$2") (pinfunction "2_P$2") (pintype "passive"))
    )
    (net (code "12") (name "BTN_ROW1") (class "Default")
      (node (ref "IC1") (pin "39") (pinfunction "PB11B/PCLKC2_1_39") (pintype "bidirectional"))
      (node (ref "R16") (pin "2") (pinfunction "2_2") (pintype "passive"))
      (node (ref "SW1") (pin "P$1") (pinfunction "1_P$1") (pintype "passive"))
      (node (ref "SW17") (pin "P$1") (pinfunction "1_P$1") (pintype "passive"))
      (node (ref "SW26") (pin "P$1") (pinfunction "1_P$1") (pintype "passive"))
      (node (ref "SW35") (pin "P$1") (pinfunction "1_P$1") (pintype "passive"))
      (node (ref "SW44") (pin "P$1") (pinfunction "1_P$1") (pintype "passive"))
      (node (ref "SW53") (pin "P$1") (pinfunction "1_P$1") (pintype "passive"))
      (node (ref "SW61") (pin "P$1") (pinfunction "1_P$1") (pintype "passive"))
      (node (ref "SW9") (pin "P$1") (pinfunction "1_P$1") (pintype "passive"))
    )
    (net (code "13") (name "BTN_ROW2") (class "Default")
      (node (ref "IC1") (pin "38") (pinfunction "PB11A/PCLKT2_1_38") (pintype "bidirectional"))
      (node (ref "R17") (pin "2") (pinfunction "2_2") (pintype "passive"))
      (node (ref "SW10") (pin "P$1") (pinfunction "1_P$1") (pintype "passive"))
      (node (ref "SW18") (pin "P$1") (pinfunction "1_P$1") (pintype "passive"))
      (node (ref "SW2") (pin "P$1") (pinfunction "1_P$1") (pintype "passive"))
      (node (ref "SW27") (pin "P$1") (pinfunction "1_P$1") (pintype "passive"))
      (node (ref "SW36") (pin "P$1") (pinfunction "1_P$1") (pintype "passive"))
      (node (ref "SW45") (pin "P$1") (pinfunction "1_P$1") (pintype "passive"))
      (node (ref "SW54") (pin "P$1") (pinfunction "1_P$1") (pintype "passive"))
      (node (ref "SW62") (pin "P$1") (pinfunction "1_P$1") (pintype "passive"))
    )
    (net (code "14") (name "BTN_ROW3") (class "Default")
      (node (ref "IC1") (pin "37") (pinfunction "PB11D_37") (pintype "bidirectional"))
      (node (ref "R18") (pin "2") (pinfunction "2_2") (pintype "passive"))
      (node (ref "SW11") (pin "P$1") (pinfunction "1_P$1") (pintype "passive"))
      (node (ref "SW19") (pin "P$1") (pinfunction "1_P$1") (pintype "passive"))
      (node (ref "SW28") (pin "P$1") (pinfunction "1_P$1") (pintype "passive"))
      (node (ref "SW3") (pin "P$1") (pinfunction "1_P$1") (pintype "passive"))
      (node (ref "SW37") (pin "P$1") (pinfunction "1_P$1") (pintype "passive"))
      (node (ref "SW46") (pin "P$1") (pinfunction "1_P$1") (pintype "passive"))
      (node (ref "SW55") (pin "P$1") (pinfunction "1_P$1") (pintype "passive"))
    )
    (net (code "15") (name "BTN_ROW4") (class "Default")
      (node (ref "IC1") (pin "36") (pinfunction "PB11C_36") (pintype "bidirectional"))
      (node (ref "R19") (pin "2") (pinfunction "2_2") (pintype "passive"))
      (node (ref "SW12") (pin "P$1") (pinfunction "1_P$1") (pintype "passive"))
      (node (ref "SW20") (pin "P$1") (pinfunction "1_P$1") (pintype "passive"))
      (node (ref "SW29") (pin "P$1") (pinfunction "1_P$1") (pintype "passive"))
      (node (ref "SW38") (pin "P$1") (pinfunction "1_P$1") (pintype "passive"))
      (node (ref "SW4") (pin "P$1") (pinfunction "1_P$1") (pintype "passive"))
      (node (ref "SW47") (pin "P$1") (pinfunction "1_P$1") (pintype "passive"))
      (node (ref "SW56") (pin "P$1") (pinfunction "1_P$1") (pintype "passive"))
      (node (ref "SW63") (pin "P$1") (pinfunction "1_P$1") (pintype "passive"))
      (node (ref "SW64") (pin "P$1") (pinfunction "1_P$1") (pintype "passive"))
    )
    (net (code "16") (name "BTN_ROW5") (class "Default")
      (node (ref "IC1") (pin "25") (pinfunction "PL10D_25") (pintype "bidirectional"))
      (node (ref "R20") (pin "2") (pinfunction "2_2") (pintype "passive"))
      (node (ref "SW13") (pin "P$1") (pinfunction "1_P$1") (pintype "passive"))
      (node (ref "SW21") (pin "P$1") (pinfunction "1_P$1") (pintype "passive"))
      (node (ref "SW30") (pin "P$1") (pinfunction "1_P$1") (pintype "passive"))
      (node (ref "SW39") (pin "P$1") (pinfunction "1_P$1") (pintype "passive"))
      (node (ref "SW48") (pin "P$1") (pinfunction "1_P$1") (pintype "passive"))
      (node (ref "SW5") (pin "P$1") (pinfunction "1_P$1") (pintype "passive"))
      (node (ref "SW57") (pin "P$1") (pinfunction "1_P$1") (pintype "passive"))
    )
    (net (code "17") (name "BTN_ROW6") (class "Default")
      (node (ref "IC1") (pin "24") (pinfunction "PL10C_24") (pintype "bidirectional"))
      (node (ref "R21") (pin "2") (pinfunction "2_2") (pintype "passive"))
      (node (ref "SW14") (pin "P$1") (pinfunction "1_P$1") (pintype "passive"))
      (node (ref "SW22") (pin "P$1") (pinfunction "1_P$1") (pintype "passive"))
      (node (ref "SW31") (pin "P$1") (pinfunction "1_P$1") (pintype "passive"))
      (node (ref "SW40") (pin "P$1") (pinfunction "1_P$1") (pintype "passive"))
      (node (ref "SW49") (pin "P$1") (pinfunction "1_P$1") (pintype "passive"))
      (node (ref "SW58") (pin "P$1") (pinfunction "1_P$1") (pintype "passive"))
      (node (ref "SW6") (pin "P$1") (pinfunction "1_P$1") (pintype "passive"))
      (node (ref "SW65") (pin "P$1") (pinfunction "1_P$1") (pintype "passive"))
    )
    (net (code "18") (name "BTN_ROW7") (class "Default")
      (node (ref "IC1") (pin "21") (pinfunction "PL9B/PCLKC3_0_21") (pintype "bidirectional"))
      (node (ref "R22") (pin "2") (pinfunction "2_2") (pintype "passive"))
      (node (ref "SW15") (pin "P$1") (pinfunction "1_P$1") (pintype "passive"))
      (node (ref "SW23") (pin "P$1") (pinfunction "1_P$1") (pintype "passive"))
      (node (ref "SW32") (pin "P$1") (pinfunction "1_P$1") (pintype "passive"))
      (node (ref "SW41") (pin "P$1") (pinfunction "1_P$1") (pintype "passive"))
      (node (ref "SW50") (pin "P$1") (pinfunction "1_P$1") (pintype "passive"))
      (node (ref "SW59") (pin "P$1") (pinfunction "1_P$1") (pintype "passive"))
      (node (ref "SW66") (pin "P$1") (pinfunction "1_P$1") (pintype "passive"))
      (node (ref "SW7") (pin "P$1") (pinfunction "1_P$1") (pintype "passive"))
    )
    (net (code "19") (name "BTN_ROW8") (class "Default")
      (node (ref "IC1") (pin "20") (pinfunction "PL9A/PCLKT3_0_20") (pintype "bidirectional"))
      (node (ref "R23") (pin "2") (pinfunction "2_2") (pintype "passive"))
      (node (ref "SW16") (pin "P$1") (pinfunction "1_P$1") (pintype "passive"))
      (node (ref "SW24") (pin "P$1") (pinfunction "1_P$1") (pintype "passive"))
      (node (ref "SW33") (pin "P$1") (pinfunction "1_P$1") (pintype "passive"))
      (node (ref "SW42") (pin "P$1") (pinfunction "1_P$1") (pintype "passive"))
      (node (ref "SW51") (pin "P$1") (pinfunction "1_P$1") (pintype "passive"))
      (node (ref "SW60") (pin "P$1") (pinfunction "1_P$1") (pintype "passive"))
      (node (ref "SW67") (pin "P$1") (pinfunction "1_P$1") (pintype "passive"))
      (node (ref "SW8") (pin "P$1") (pinfunction "1_P$1") (pintype "passive"))
    )
    (net (code "20") (name "BTN_ROW9") (class "Default")
      (node (ref "IC1") (pin "19") (pinfunction "PL8D_19") (pintype "bidirectional"))
      (node (ref "R24") (pin "2") (pinfunction "2_2") (pintype "passive"))
      (node (ref "SW25") (pin "P$1") (pinfunction "1_P$1") (pintype "passive"))
      (node (ref "SW34") (pin "P$1") (pinfunction "1_P$1") (pintype "passive"))
      (node (ref "SW43") (pin "P$1") (pinfunction "1_P$1") (pintype "passive"))
      (node (ref "SW52") (pin "P$1") (pinfunction "1_P$1") (pintype "passive"))
    )
    (net (code "21") (name "CPLD_JTAGENB") (class "Default")
      (node (ref "IC1") (pin "82") (pinfunction "PT15C/JTAGENB_82") (pintype "bidirectional"))
      (node (ref "R5") (pin "1") (pinfunction "1_1") (pintype "passive"))
    )
    (net (code "22") (name "CPLD_TCK") (class "Default")
      (node (ref "IC1") (pin "91") (pinfunction "PT11C/TCK_91") (pintype "bidirectional"))
      (node (ref "J1") (pin "4") (pinfunction "4_4") (pintype "bidirectional"))
    )
    (net (code "23") (name "CPLD_TDI") (class "Default")
      (node (ref "IC1") (pin "94") (pinfunction "PT10D/TDI_94") (pintype "bidirectional"))
      (node (ref "J1") (pin "3") (pinfunction "3_3") (pintype "bidirectional"))
    )
    (net (code "24") (name "CPLD_TDO") (class "Default")
      (node (ref "IC1") (pin "95") (pinfunction "PT10C/TDO_95") (pintype "bidirectional"))
      (node (ref "J1") (pin "2") (pinfunction "2_2") (pintype "bidirectional"))
    )
    (net (code "25") (name "CPLD_TMS") (class "Default")
      (node (ref "IC1") (pin "90") (pinfunction "PT11D/TMS_90") (pintype "bidirectional"))
      (node (ref "J1") (pin "5") (pinfunction "5_5") (pintype "bidirectional"))
    )
    (net (code "26") (name "DCLK") (class "Default")
      (node (ref "IC1") (pin "12") (pinfunction "PL5A/PCLKT3_1_12") (pintype "bidirectional"))
      (node (ref "X2") (pin "30") (pinfunction "30_30") (pintype "passive"))
    )
    (net (code "27") (name "DE") (class "Default")
      (node (ref "IC1") (pin "15") (pinfunction "PL5D_15") (pintype "bidirectional"))
      (node (ref "X2") (pin "34") (pinfunction "34_34") (pintype "passive"))
    )
    (net (code "28") (name "G0") (class "Default")
      (node (ref "IC1") (pin "1") (pinfunction "PL2C/L_GPLLT_IN_1") (pintype "bidirectional"))
      (node (ref "X2") (pin "13") (pinfunction "13_13") (pintype "passive"))
    )
    (net (code "29") (name "G1") (class "Default")
      (node (ref "IC1") (pin "2") (pinfunction "PL2D/L_GPLLC_IN_2") (pintype "bidirectional"))
      (node (ref "X2") (pin "14") (pinfunction "14_14") (pintype "passive"))
    )
    (net (code "30") (name "G2") (class "Default")
      (node (ref "IC1") (pin "3") (pinfunction "PL3A/PCLKT3_2_3") (pintype "bidirectional"))
      (node (ref "X2") (pin "15") (pinfunction "15_15") (pintype "passive"))
    )
    (net (code "31") (name "G3") (class "Default")
      (node (ref "IC1") (pin "4") (pinfunction "PL3B/PCLKC3_2_4") (pintype "bidirectional"))
      (node (ref "X2") (pin "16") (pinfunction "16_16") (pintype "passive"))
    )
    (net (code "32") (name "G4") (class "Default")
      (node (ref "IC1") (pin "7") (pinfunction "PL3C_7") (pintype "bidirectional"))
      (node (ref "X2") (pin "17") (pinfunction "17_17") (pintype "passive"))
    )
    (net (code "33") (name "G5") (class "Default")
      (node (ref "IC1") (pin "8") (pinfunction "PL3D_8") (pintype "bidirectional"))
      (node (ref "X2") (pin "18") (pinfunction "18_18") (pintype "passive"))
    )
    (net (code "34") (name "G6") (class "Default")
      (node (ref "IC1") (pin "9") (pinfunction "PL4A_9") (pintype "bidirectional"))
      (node (ref "X2") (pin "19") (pinfunction "19_19") (pintype "passive"))
    )
    (net (code "35") (name "G7") (class "Default")
      (node (ref "IC1") (pin "10") (pinfunction "PL4B_10") (pintype "bidirectional"))
      (node (ref "X2") (pin "20") (pinfunction "20_20") (pintype "passive"))
    )
    (net (code "36") (name "GND") (class "Default")
      (node (ref "C1") (pin "2") (pinfunction "2_2") (pintype "passive"))
      (node (ref "C11") (pin "2") (pinfunction "2_2") (pintype "passive"))
      (node (ref "C12") (pin "2") (pinfunction "2_2") (pintype "passive"))
      (node (ref "C13") (pin "2") (pinfunction "2_2") (pintype "passive"))
      (node (ref "C2") (pin "2") (pinfunction "2_2") (pintype "passive"))
      (node (ref "C3") (pin "2") (pinfunction "2_2") (pintype "passive"))
      (node (ref "C4") (pin "2") (pinfunction "2_2") (pintype "passive"))
      (node (ref "C5") (pin "2") (pinfunction "2_2") (pintype "passive"))
      (node (ref "C6") (pin "2") (pinfunction "2_2") (pintype "passive"))
      (node (ref "C7") (pin "2") (pinfunction "2_2") (pintype "passive"))
      (node (ref "C8") (pin "1") (pinfunction "1_1") (pintype "passive"))
      (node (ref "C9") (pin "2") (pinfunction "2_2") (pintype "passive"))
      (node (ref "IC1") (pin "22") (pinfunction "GND_22") (pintype "power_in"))
      (node (ref "IC1") (pin "33") (pinfunction "GND_33") (pintype "power_in"))
      (node (ref "IC1") (pin "44") (pinfunction "GND_44") (pintype "power_in"))
      (node (ref "IC1") (pin "56") (pinfunction "GND_56") (pintype "power_in"))
      (node (ref "IC1") (pin "6") (pinfunction "GND_6") (pintype "power_in"))
      (node (ref "IC1") (pin "72") (pinfunction "GND_72") (pintype "power_in"))
      (node (ref "IC1") (pin "79") (pinfunction "GND_79") (pintype "power_in"))
      (node (ref "IC1") (pin "92") (pinfunction "GND_92") (pintype "power_in"))
      (node (ref "IC2") (pin "1") (pinfunction "GND_1") (pintype "passive"))
      (node (ref "IC2") (pin "4") (pinfunction "V-_4") (pintype "power_in"))
      (node (ref "J1") (pin "1") (pinfunction "1_1") (pintype "bidirectional"))
      (node (ref "J3") (pin "3") (pinfunction "3_3") (pintype "passive"))
      (node (ref "J3") (pin "5") (pinfunction "5_5") (pintype "passive"))
      (node (ref "J3") (pin "9") (pinfunction "9_9") (pintype "passive"))
      (node (ref "Q1") (pin "1") (pinfunction "G_1") (pintype "passive"))
      (node (ref "R1") (pin "1") (pinfunction "1_1") (pintype "passive"))
      (node (ref "R11") (pin "2") (pinfunction "2_2") (pintype "passive"))
      (node (ref "R14") (pin "1") (pinfunction "1_1") (pintype "passive"))
      (node (ref "R15") (pin "1") (pinfunction "1_1") (pintype "passive"))
      (node (ref "R7") (pin "1") (pinfunction "1_1") (pintype "passive"))
      (node (ref "R8") (pin "1") (pinfunction "1_1") (pintype "passive"))
      (node (ref "TP1") (pin "P$1") (pinfunction "1_P$1") (pintype "bidirectional"))
      (node (ref "U1") (pin "41") (pinfunction "VSS_41") (pintype "bidirectional"))
      (node (ref "U1") (pin "5") (pinfunction "VSS_5") (pintype "bidirectional"))
      (node (ref "U2") (pin "4") (pinfunction "GND_4") (pintype "bidirectional"))
      (node (ref "U3") (pin "2") (pinfunction "GND_2") (pintype "power_in"))
      (node (ref "X1") (pin "5") (pinfunction "5_5") (pintype "passive"))
      (node (ref "X2") (pin "1") (pinfunction "1_1") (pintype "passive"))
      (node (ref "X2") (pin "10") (pinfunction "10_10") (pintype "passive"))
      (node (ref "X2") (pin "11") (pinfunction "11_11") (pintype "passive"))
      (node (ref "X2") (pin "12") (pinfunction "12_12") (pintype "passive"))
      (node (ref "X2") (pin "21") (pinfunction "21_21") (pintype "passive"))
      (node (ref "X2") (pin "22") (pinfunction "22_22") (pintype "passive"))
      (node (ref "X2") (pin "23") (pinfunction "23_23") (pintype "passive"))
      (node (ref "X2") (pin "24") (pinfunction "24_24") (pintype "passive"))
      (node (ref "X2") (pin "25") (pinfunction "25_25") (pintype "passive"))
      (node (ref "X2") (pin "26") (pinfunction "26_26") (pintype "passive"))
      (node (ref "X2") (pin "27") (pinfunction "27_27") (pintype "passive"))
      (node (ref "X2") (pin "28") (pinfunction "28_28") (pintype "passive"))
      (node (ref "X2") (pin "29") (pinfunction "29_29") (pintype "passive"))
      (node (ref "X2") (pin "3") (pinfunction "3_3") (pintype "passive"))
      (node (ref "X2") (pin "5") (pinfunction "5_5") (pintype "passive"))
      (node (ref "X2") (pin "6") (pinfunction "6_6") (pintype "passive"))
      (node (ref "X2") (pin "7") (pinfunction "7_7") (pintype "passive"))
      (node (ref "X2") (pin "8") (pinfunction "8_8") (pintype "passive"))
      (node (ref "X2") (pin "9") (pinfunction "9_9") (pintype "passive"))
      (node (ref "Y1") (pin "2") (pinfunction "GND_2") (pintype "bidirectional"))
    )
    (net (code "37") (name "HSYNC") (class "Default")
      (node (ref "IC1") (pin "13") (pinfunction "PL5B/PCLKC3_1_13") (pintype "bidirectional"))
      (node (ref "X2") (pin "32") (pinfunction "32_32") (pintype "passive"))
    )
    (net (code "38") (name "LCD_NRESET") (class "Default")
      (node (ref "IC2") (pin "7") (pinfunction "OUT_7") (pintype "output"))
      (node (ref "R9") (pin "2") (pinfunction "2_2") (pintype "passive"))
      (node (ref "X2") (pin "36") (pinfunction "36_36") (pintype "passive"))
    )
    (net (code "39") (name "LED1") (class "Default")
      (node (ref "IC1") (pin "66") (pinfunction "PR4D_66") (pintype "bidirectional"))
      (node (ref "R25") (pin "1") (pinfunction "1_1") (pintype "passive"))
    )
    (net (code "40") (name "LED2") (class "Default")
      (node (ref "IC1") (pin "67") (pinfunction "PR4C_67") (pintype "bidirectional"))
      (node (ref "R26") (pin "1") (pinfunction "1_1") (pintype "passive"))
    )
    (net (code "41") (name "LED3") (class "Default")
      (node (ref "IC1") (pin "68") (pinfunction "PR4B_68") (pintype "bidirectional"))
      (node (ref "R27") (pin "1") (pinfunction "1_1") (pintype "passive"))
    )
    (net (code "42") (name "LED4") (class "Default")
      (node (ref "IC1") (pin "69") (pinfunction "PR4A_69") (pintype "bidirectional"))
      (node (ref "R28") (pin "1") (pinfunction "1_1") (pintype "passive"))
    )
    (net (code "43") (name "MCU_LED") (class "Default")
      (node (ref "D1") (pin "A") (pinfunction "A_A") (pintype "passive"))
      (node (ref "U1") (pin "43") (pinfunction "PIO3_2_43") (pintype "bidirectional"))
    )
    (net (code "44") (name "MISO") (class "Default")
      (node (ref "IC1") (pin "99") (pinfunction "PT9A_99") (pintype "bidirectional"))
      (node (ref "U1") (pin "27") (pinfunction "PIO0_8/MISO0/CT16B0_MAT0_27") (pintype "bidirectional"))
    )
    (net (code "45") (name "NRESET") (class "Default")
      (node (ref "C5") (pin "1") (pinfunction "1_1") (pintype "passive"))
      (node (ref "J3") (pin "10") (pinfunction "10_10") (pintype "passive"))
      (node (ref "R6") (pin "1") (pinfunction "1_1") (pintype "passive"))
      (node (ref "U1") (pin "3") (pinfunction "NRESET/PIO0_0_3") (pintype "bidirectional"))
    )
    (net (code "46") (name "Net-(D1-PadC)") (class "Default")
      (node (ref "D1") (pin "C") (pinfunction "C_C") (pintype "passive"))
      (node (ref "R8") (pin "2") (pinfunction "2_2") (pintype "passive"))
    )
    (net (code "47") (name "Net-(D3-PadC)") (class "Default")
      (node (ref "D3") (pin "C") (pinfunction "C_C") (pintype "passive"))
      (node (ref "R25") (pin "2") (pinfunction "2_2") (pintype "passive"))
    )
    (net (code "48") (name "Net-(D4-PadC)") (class "Default")
      (node (ref "D4") (pin "C") (pinfunction "C_C") (pintype "passive"))
      (node (ref "R26") (pin "2") (pinfunction "2_2") (pintype "passive"))
    )
    (net (code "49") (name "Net-(D5-PadC)") (class "Default")
      (node (ref "D5") (pin "C") (pinfunction "C_C") (pintype "passive"))
      (node (ref "R27") (pin "2") (pinfunction "2_2") (pintype "passive"))
    )
    (net (code "50") (name "Net-(D6-PadC)") (class "Default")
      (node (ref "D6") (pin "C") (pinfunction "C_C") (pintype "passive"))
      (node (ref "R28") (pin "2") (pinfunction "2_2") (pintype "passive"))
    )
    (net (code "51") (name "Net-(IC2-+IN)") (class "Default")
      (node (ref "C8") (pin "2") (pinfunction "2_2") (pintype "passive"))
      (node (ref "IC2") (pin "2") (pinfunction "+IN_2") (pintype "input"))
      (node (ref "R12") (pin "1") (pinfunction "1_1") (pintype "passive"))
    )
    (net (code "52") (name "Net-(IC2--IN)") (class "Default")
      (node (ref "IC2") (pin "3") (pinfunction "-IN_3") (pintype "input"))
      (node (ref "R10") (pin "2") (pinfunction "2_2") (pintype "passive"))
      (node (ref "R11") (pin "1") (pinfunction "1_1") (pintype "passive"))
    )
    (net (code "53") (name "Net-(R15-Pad2)") (class "Default")
      (node (ref "R15") (pin "2") (pinfunction "2_2") (pintype "passive"))
      (node (ref "R16") (pin "1") (pinfunction "1_1") (pintype "passive"))
      (node (ref "R17") (pin "1") (pinfunction "1_1") (pintype "passive"))
      (node (ref "R18") (pin "1") (pinfunction "1_1") (pintype "passive"))
      (node (ref "R19") (pin "1") (pinfunction "1_1") (pintype "passive"))
      (node (ref "R20") (pin "1") (pinfunction "1_1") (pintype "passive"))
      (node (ref "R21") (pin "1") (pinfunction "1_1") (pintype "passive"))
      (node (ref "R22") (pin "1") (pinfunction "1_1") (pintype "passive"))
      (node (ref "R23") (pin "1") (pinfunction "1_1") (pintype "passive"))
      (node (ref "R24") (pin "1") (pinfunction "1_1") (pintype "passive"))
    )
    (net (code "54") (name "Net-(U2-FB)") (class "Default")
      (node (ref "C10") (pin "2") (pinfunction "2_2") (pintype "passive"))
      (node (ref "R13") (pin "1") (pinfunction "1_1") (pintype "passive"))
      (node (ref "R14") (pin "2") (pinfunction "2_2") (pintype "passive"))
      (node (ref "U2") (pin "2") (pinfunction "FB_2") (pintype "bidirectional"))
    )
    (net (code "55") (name "Net-(U2-LX)") (class "Default")
      (node (ref "D2") (pin "A") (pinfunction "A_A") (pintype "passive"))
      (node (ref "L1") (pin "1") (pinfunction "1_1") (pintype "passive"))
      (node (ref "U2") (pin "5") (pinfunction "LX_5") (pintype "bidirectional"))
    )
    (net (code "56") (name "Net-(X1B-S1)") (class "Default")
      (node (ref "C1") (pin "1") (pinfunction "1_1") (pintype "passive"))
      (node (ref "R1") (pin "2") (pinfunction "2_2") (pintype "passive"))
      (node (ref "X1") (pin "M1") (pinfunction "S1_M1") (pintype "passive"))
      (node (ref "X1") (pin "M2") (pinfunction "S2_M2") (pintype "passive"))
      (node (ref "X1") (pin "M3") (pinfunction "S3_M3") (pintype "passive"))
      (node (ref "X1") (pin "M4") (pinfunction "S4_M4") (pintype "passive"))
    )
    (net (code "57") (name "SCK") (class "Default")
      (node (ref "IC1") (pin "97") (pinfunction "PT10A_97") (pintype "bidirectional"))
      (node (ref "U1") (pin "31") (pinfunction "PIO2_11/SCK0_31") (pintype "bidirectional"))
    )
    (net (code "58") (name "SSEL") (class "Default")
      (node (ref "IC1") (pin "96") (pinfunction "PT10B_96") (pintype "bidirectional"))
      (node (ref "U1") (pin "10") (pinfunction "PIO0_2/SSEL0/CT16B0_CAP0_10") (pintype "bidirectional"))
    )
    (net (code "59") (name "SWCLK") (class "Default")
      (node (ref "J3") (pin "4") (pinfunction "4_4") (pintype "passive"))
      (node (ref "U1") (pin "29") (pinfunction "SWCLK/PIO0_10/SCK0/CT16B0_MAT2_29") (pintype "bidirectional"))
    )
    (net (code "60") (name "SWDIO") (class "Default")
      (node (ref "J3") (pin "2") (pinfunction "2_2") (pintype "passive"))
      (node (ref "U1") (pin "39") (pinfunction "SWDIO/PIO1_3/AD4/CT32B1_MAT2_39") (pintype "bidirectional"))
    )
    (net (code "61") (name "SWO{slash}MOSI") (class "Default")
      (node (ref "IC1") (pin "98") (pinfunction "PT9B_98") (pintype "bidirectional"))
      (node (ref "J3") (pin "6") (pinfunction "6_6") (pintype "passive"))
      (node (ref "U1") (pin "28") (pinfunction "PIO0_9/MOSI0/CT16B0_MAT1/SWO_28") (pintype "bidirectional"))
    )
    (net (code "62") (name "USB_DX_N") (class "Default")
      (node (ref "R2") (pin "2") (pinfunction "2_2") (pintype "passive"))
      (node (ref "U1") (pin "19") (pinfunction "USB_DM_19") (pintype "bidirectional"))
    )
    (net (code "63") (name "USB_DX_P") (class "Default")
      (node (ref "R3") (pin "2") (pinfunction "2_2") (pintype "passive"))
      (node (ref "R4") (pin "2") (pinfunction "2_2") (pintype "passive"))
      (node (ref "U1") (pin "20") (pinfunction "USB_DP_20") (pintype "bidirectional"))
    )
    (net (code "64") (name "USB_D_N") (class "Default")
      (node (ref "R2") (pin "1") (pinfunction "1_1") (pintype "passive"))
      (node (ref "X1") (pin "2") (pinfunction "2_2") (pintype "passive"))
    )
    (net (code "65") (name "USB_D_P") (class "Default")
      (node (ref "R3") (pin "1") (pinfunction "1_1") (pintype "passive"))
      (node (ref "X1") (pin "3") (pinfunction "3_3") (pintype "passive"))
    )
    (net (code "66") (name "USB_VBUS{slash}ISP_MODE") (class "Default")
      (node (ref "J2") (pin "1") (pinfunction "1_1") (pintype "passive"))
      (node (ref "R7") (pin "2") (pinfunction "2_2") (pintype "passive"))
      (node (ref "U1") (pin "14") (pinfunction "PIO0_3/USB_VBUS_14") (pintype "bidirectional"))
    )
    (net (code "67") (name "USB_VCC") (class "Default")
      (node (ref "C2") (pin "1") (pinfunction "1_1") (pintype "passive"))
      (node (ref "Q1") (pin "2") (pinfunction "S_2") (pintype "passive"))
      (node (ref "X1") (pin "1") (pinfunction "1_1") (pintype "passive"))
    )
    (net (code "68") (name "VLED+") (class "Default")
      (node (ref "C10") (pin "1") (pinfunction "1_1") (pintype "passive"))
      (node (ref "C11") (pin "1") (pinfunction "1_1") (pintype "passive"))
      (node (ref "D2") (pin "C") (pinfunction "C_C") (pintype "passive"))
      (node (ref "R13") (pin "2") (pinfunction "2_2") (pintype "passive"))
      (node (ref "TP4") (pin "P$1") (pinfunction "1_P$1") (pintype "bidirectional"))
      (node (ref "X2") (pin "2") (pinfunction "2_2") (pintype "passive"))
    )
    (net (code "69") (name "VSYNC") (class "Default")
      (node (ref "IC1") (pin "14") (pinfunction "PL5C_14") (pintype "bidirectional"))
      (node (ref "X2") (pin "33") (pinfunction "33_33") (pintype "passive"))
    )
    (net (code "70") (name "XTALIN") (class "Default")
      (node (ref "C6") (pin "1") (pinfunction "1_1") (pintype "passive"))
      (node (ref "U1") (pin "6") (pinfunction "XTALIN_6") (pintype "bidirectional"))
      (node (ref "XTAL1") (pin "1") (pinfunction "1_1") (pintype "passive"))
    )
    (net (code "71") (name "XTALOUT") (class "Default")
      (node (ref "C7") (pin "1") (pinfunction "1_1") (pintype "passive"))
      (node (ref "U1") (pin "7") (pinfunction "XTALOUT_7") (pintype "bidirectional"))
      (node (ref "XTAL1") (pin "2") (pinfunction "2_2") (pintype "passive"))
    )
    (net (code "72") (name "unconnected-(IC1-NC-Pad89)") (class "Default")
      (node (ref "IC1") (pin "89") (pinfunction "NC_89") (pintype "no_connect"))
    )
    (net (code "73") (name "unconnected-(IC1-PB15A-Pad40)") (class "Default")
      (node (ref "IC1") (pin "40") (pinfunction "PB15A_40") (pintype "bidirectional"))
    )
    (net (code "74") (name "unconnected-(IC1-PB15B-Pad41)") (class "Default")
      (node (ref "IC1") (pin "41") (pinfunction "PB15B_41") (pintype "bidirectional"))
    )
    (net (code "75") (name "unconnected-(IC1-PB18A-Pad42)") (class "Default")
      (node (ref "IC1") (pin "42") (pinfunction "PB18A_42") (pintype "bidirectional"))
    )
    (net (code "76") (name "unconnected-(IC1-PB18B-Pad43)") (class "Default")
      (node (ref "IC1") (pin "43") (pinfunction "PB18B_43") (pintype "bidirectional"))
    )
    (net (code "77") (name "unconnected-(IC1-PB18C-Pad45)") (class "Default")
      (node (ref "IC1") (pin "45") (pinfunction "PB18C_45") (pintype "bidirectional"))
    )
    (net (code "78") (name "unconnected-(IC1-PB18D-Pad47)") (class "Default")
      (node (ref "IC1") (pin "47") (pinfunction "PB18D_47") (pintype "bidirectional"))
    )
    (net (code "79") (name "unconnected-(IC1-PB20C{slash}SN-Pad48)") (class "Default")
      (node (ref "IC1") (pin "48") (pinfunction "PB20C/SN_48") (pintype "bidirectional"))
    )
    (net (code "80") (name "unconnected-(IC1-PB20D{slash}SI{slash}SISPI-Pad49)") (class "Default")
      (node (ref "IC1") (pin "49") (pinfunction "PB20D/SI/SISPI_49") (pintype "bidirectional"))
    )
    (net (code "81") (name "unconnected-(IC1-PL8A-Pad16)") (class "Default")
      (node (ref "IC1") (pin "16") (pinfunction "PL8A_16") (pintype "bidirectional"))
    )
    (net (code "82") (name "unconnected-(IC1-PL8B-Pad17)") (class "Default")
      (node (ref "IC1") (pin "17") (pinfunction "PL8B_17") (pintype "bidirectional"))
    )
    (net (code "83") (name "unconnected-(IC1-PL8C-Pad18)") (class "Default")
      (node (ref "IC1") (pin "18") (pinfunction "PL8C_18") (pintype "bidirectional"))
    )
    (net (code "84") (name "unconnected-(IC1-PR2A-Pad75)") (class "Default")
      (node (ref "IC1") (pin "75") (pinfunction "PR2A_75") (pintype "bidirectional"))
    )
    (net (code "85") (name "unconnected-(IC1-PR2B-Pad74)") (class "Default")
      (node (ref "IC1") (pin "74") (pinfunction "PR2B_74") (pintype "bidirectional"))
    )
    (net (code "86") (name "unconnected-(IC1-PR3A-Pad71)") (class "Default")
      (node (ref "IC1") (pin "71") (pinfunction "PR3A_71") (pintype "bidirectional"))
    )
    (net (code "87") (name "unconnected-(IC1-PR3B-Pad70)") (class "Default")
      (node (ref "IC1") (pin "70") (pinfunction "PR3B_70") (pintype "bidirectional"))
    )
    (net (code "88") (name "unconnected-(IC1-PR5A-Pad65)") (class "Default")
      (node (ref "IC1") (pin "65") (pinfunction "PR5A_65") (pintype "bidirectional"))
    )
    (net (code "89") (name "unconnected-(IC1-PR5B-Pad64)") (class "Default")
      (node (ref "IC1") (pin "64") (pinfunction "PR5B_64") (pintype "bidirectional"))
    )
    (net (code "90") (name "unconnected-(IC1-PR5D{slash}PCLKC1_0-Pad62)") (class "Default")
      (node (ref "IC1") (pin "62") (pinfunction "PR5D/PCLKC1_0_62") (pintype "bidirectional"))
    )
    (net (code "91") (name "unconnected-(IC1-PR8A-Pad61)") (class "Default")
      (node (ref "IC1") (pin "61") (pinfunction "PR8A_61") (pintype "bidirectional"))
    )
    (net (code "92") (name "unconnected-(IC1-PR8C-Pad60)") (class "Default")
      (node (ref "IC1") (pin "60") (pinfunction "PR8C_60") (pintype "bidirectional"))
    )
    (net (code "93") (name "unconnected-(IC1-PR8D-Pad59)") (class "Default")
      (node (ref "IC1") (pin "59") (pinfunction "PR8D_59") (pintype "bidirectional"))
    )
    (net (code "94") (name "unconnected-(IC1-PR9A-Pad58)") (class "Default")
      (node (ref "IC1") (pin "58") (pinfunction "PR9A_58") (pintype "bidirectional"))
    )
    (net (code "95") (name "unconnected-(IC1-PR9B-Pad57)") (class "Default")
      (node (ref "IC1") (pin "57") (pinfunction "PR9B_57") (pintype "bidirectional"))
    )
    (net (code "96") (name "unconnected-(IC1-PR9C-Pad54)") (class "Default")
      (node (ref "IC1") (pin "54") (pinfunction "PR9C_54") (pintype "bidirectional"))
    )
    (net (code "97") (name "unconnected-(IC1-PR9D-Pad53)") (class "Default")
      (node (ref "IC1") (pin "53") (pinfunction "PR9D_53") (pintype "bidirectional"))
    )
    (net (code "98") (name "unconnected-(IC1-PR10C-Pad52)") (class "Default")
      (node (ref "IC1") (pin "52") (pinfunction "PR10C_52") (pintype "bidirectional"))
    )
    (net (code "99") (name "unconnected-(IC1-PR10D-Pad51)") (class "Default")
      (node (ref "IC1") (pin "51") (pinfunction "PR10D_51") (pintype "bidirectional"))
    )
    (net (code "100") (name "unconnected-(IC1-PT12A{slash}PCLKT0_1-Pad88)") (class "Default")
      (node (ref "IC1") (pin "88") (pinfunction "PT12A/PCLKT0_1_88") (pintype "bidirectional"))
    )
    (net (code "101") (name "unconnected-(IC1-PT12B{slash}PCLKC0_1-Pad87)") (class "Default")
      (node (ref "IC1") (pin "87") (pinfunction "PT12B/PCLKC0_1_87") (pintype "bidirectional"))
    )
    (net (code "102") (name "unconnected-(IC1-PT12C{slash}SCL{slash}PCLKT0_0-Pad86)") (class "Default")
      (node (ref "IC1") (pin "86") (pinfunction "PT12C/SCL/PCLKT0_0_86") (pintype "bidirectional"))
    )
    (net (code "103") (name "unconnected-(IC1-PT12D{slash}SDA{slash}PCLKC0_0-Pad85)") (class "Default")
      (node (ref "IC1") (pin "85") (pinfunction "PT12D/SDA/PCLKC0_0_85") (pintype "bidirectional"))
    )
    (net (code "104") (name "unconnected-(IC1-PT15A-Pad84)") (class "Default")
      (node (ref "IC1") (pin "84") (pinfunction "PT15A_84") (pintype "bidirectional"))
    )
    (net (code "105") (name "unconnected-(IC1-PT15B-Pad83)") (class "Default")
      (node (ref "IC1") (pin "83") (pinfunction "PT15B_83") (pintype "bidirectional"))
    )
    (net (code "106") (name "unconnected-(IC1-PT15D{slash}PROGRAMN-Pad81)") (class "Default")
      (node (ref "IC1") (pin "81") (pinfunction "PT15D/PROGRAMN_81") (pintype "bidirectional"))
    )
    (net (code "107") (name "unconnected-(IC1-PT16C-Pad78)") (class "Default")
      (node (ref "IC1") (pin "78") (pinfunction "PT16C_78") (pintype "bidirectional"))
    )
    (net (code "108") (name "unconnected-(IC1-PT17C{slash}INITN-Pad77)") (class "Default")
      (node (ref "IC1") (pin "77") (pinfunction "PT17C/INITN_77") (pintype "bidirectional"))
    )
    (net (code "109") (name "unconnected-(IC1-PT17D{slash}DONE-Pad76)") (class "Default")
      (node (ref "IC1") (pin "76") (pinfunction "PT17D/DONE_76") (pintype "bidirectional"))
    )
    (net (code "110") (name "unconnected-(IC2-ON-Pad5)") (class "Default")
      (node (ref "IC2") (pin "5") (pinfunction "ON_5") (pintype "passive"))
    )
    (net (code "111") (name "unconnected-(IC2-ON{slash}STR-Pad6)") (class "Default")
      (node (ref "IC2") (pin "6") (pinfunction "ON/STR_6") (pintype "passive"))
    )
    (net (code "112") (name "unconnected-(J3-Pad7)") (class "Default")
      (node (ref "J3") (pin "7") (pinfunction "7_7") (pintype "passive"))
    )
    (net (code "113") (name "unconnected-(J3-Pad8)") (class "Default")
      (node (ref "J3") (pin "8") (pinfunction "8_8") (pintype "passive"))
    )
    (net (code "114") (name "unconnected-(U1-PIO0_1{slash}CLKOUT{slash}CT32B0_MAT2{slash}USB_FTOGGLE-Pad4)") (class "Default")
      (node (ref "U1") (pin "4") (pinfunction "PIO0_1/CLKOUT/CT32B0_MAT2/USB_FTOGGLE_4") (pintype "bidirectional"))
    )
    (net (code "115") (name "unconnected-(U1-PIO0_4{slash}SCL-Pad15)") (class "Default")
      (node (ref "U1") (pin "15") (pinfunction "PIO0_4/SCL_15") (pintype "bidirectional"))
    )
    (net (code "116") (name "unconnected-(U1-PIO0_5{slash}SDA-Pad16)") (class "Default")
      (node (ref "U1") (pin "16") (pinfunction "PIO0_5/SDA_16") (pintype "bidirectional"))
    )
    (net (code "117") (name "unconnected-(U1-PIO0_6{slash}NUSB_CONNECT{slash}SCK-Pad22)") (class "Default")
      (node (ref "U1") (pin "22") (pinfunction "PIO0_6/NUSB_CONNECT/SCK_22") (pintype "bidirectional"))
    )
    (net (code "118") (name "unconnected-(U1-PIO0_7{slash}NCTS-Pad23)") (class "Default")
      (node (ref "U1") (pin "23") (pinfunction "PIO0_7/NCTS_23") (pintype "bidirectional"))
    )
    (net (code "119") (name "unconnected-(U1-PIO1_4{slash}AD5{slash}CT32B1_MAT3{slash}WAKEUP-Pad40)") (class "Default")
      (node (ref "U1") (pin "40") (pinfunction "PIO1_4/AD5/CT32B1_MAT3/WAKEUP_40") (pintype "bidirectional"))
    )
    (net (code "120") (name "unconnected-(U1-PIO1_5{slash}NRTS{slash}CT32B0_CAP0-Pad45)") (class "Default")
      (node (ref "U1") (pin "45") (pinfunction "PIO1_5/NRTS/CT32B0_CAP0_45") (pintype "bidirectional"))
    )
    (net (code "121") (name "unconnected-(U1-PIO1_6{slash}RXD{slash}CT32B0_MAT0-Pad46)") (class "Default")
      (node (ref "U1") (pin "46") (pinfunction "PIO1_6/RXD/CT32B0_MAT0_46") (pintype "bidirectional"))
    )
    (net (code "122") (name "unconnected-(U1-PIO1_7{slash}TXD{slash}CT32B0_MAT1-Pad47)") (class "Default")
      (node (ref "U1") (pin "47") (pinfunction "PIO1_7/TXD/CT32B0_MAT1_47") (pintype "bidirectional"))
    )
    (net (code "123") (name "unconnected-(U1-PIO1_8{slash}CT16B1_CAP0-Pad9)") (class "Default")
      (node (ref "U1") (pin "9") (pinfunction "PIO1_8/CT16B1_CAP0_9") (pintype "bidirectional"))
    )
    (net (code "124") (name "unconnected-(U1-PIO1_9{slash}CT16B1_MAT0-Pad17)") (class "Default")
      (node (ref "U1") (pin "17") (pinfunction "PIO1_9/CT16B1_MAT0_17") (pintype "bidirectional"))
    )
    (net (code "125") (name "unconnected-(U1-PIO1_10{slash}AD6{slash}CT16B1_MAT1-Pad30)") (class "Default")
      (node (ref "U1") (pin "30") (pinfunction "PIO1_10/AD6/CT16B1_MAT1_30") (pintype "bidirectional"))
    )
    (net (code "126") (name "unconnected-(U1-PIO1_11{slash}AD7-Pad42)") (class "Default")
      (node (ref "U1") (pin "42") (pinfunction "PIO1_11/AD7_42") (pintype "bidirectional"))
    )
    (net (code "127") (name "unconnected-(U1-PIO2_0_NDTR-Pad2)") (class "Default")
      (node (ref "U1") (pin "2") (pinfunction "PIO2_0_NDTR_2") (pintype "bidirectional"))
    )
    (net (code "128") (name "unconnected-(U1-PIO2_1{slash}NDSR-Pad13)") (class "Default")
      (node (ref "U1") (pin "13") (pinfunction "PIO2_1/NDSR_13") (pintype "bidirectional"))
    )
    (net (code "129") (name "unconnected-(U1-PIO2_2{slash}NDCD-Pad26)") (class "Default")
      (node (ref "U1") (pin "26") (pinfunction "PIO2_2/NDCD_26") (pintype "bidirectional"))
    )
    (net (code "130") (name "unconnected-(U1-PIO2_3{slash}NRI-Pad38)") (class "Default")
      (node (ref "U1") (pin "38") (pinfunction "PIO2_3/NRI_38") (pintype "bidirectional"))
    )
    (net (code "131") (name "unconnected-(U1-PIO2_4-Pad18)") (class "Default")
      (node (ref "U1") (pin "18") (pinfunction "PIO2_4_18") (pintype "bidirectional"))
    )
    (net (code "132") (name "unconnected-(U1-PIO2_5-Pad21)") (class "Default")
      (node (ref "U1") (pin "21") (pinfunction "PIO2_5_21") (pintype "bidirectional"))
    )
    (net (code "133") (name "unconnected-(U1-PIO2_6-Pad1)") (class "Default")
      (node (ref "U1") (pin "1") (pinfunction "PIO2_6_1") (pintype "bidirectional"))
    )
    (net (code "134") (name "unconnected-(U1-PIO2_7-Pad11)") (class "Default")
      (node (ref "U1") (pin "11") (pinfunction "PIO2_7_11") (pintype "bidirectional"))
    )
    (net (code "135") (name "unconnected-(U1-PIO2_8-Pad12)") (class "Default")
      (node (ref "U1") (pin "12") (pinfunction "PIO2_8_12") (pintype "bidirectional"))
    )
    (net (code "136") (name "unconnected-(U1-PIO2_9-Pad24)") (class "Default")
      (node (ref "U1") (pin "24") (pinfunction "PIO2_9_24") (pintype "bidirectional"))
    )
    (net (code "137") (name "unconnected-(U1-PIO2_10-Pad25)") (class "Default")
      (node (ref "U1") (pin "25") (pinfunction "PIO2_10_25") (pintype "bidirectional"))
    )
    (net (code "138") (name "unconnected-(U1-PIO3_0-Pad36)") (class "Default")
      (node (ref "U1") (pin "36") (pinfunction "PIO3_0_36") (pintype "bidirectional"))
    )
    (net (code "139") (name "unconnected-(U1-PIO3_1-Pad37)") (class "Default")
      (node (ref "U1") (pin "37") (pinfunction "PIO3_1_37") (pintype "bidirectional"))
    )
    (net (code "140") (name "unconnected-(U1-PIO3_3-Pad48)") (class "Default")
      (node (ref "U1") (pin "48") (pinfunction "PIO3_3_48") (pintype "bidirectional"))
    )
    (net (code "141") (name "unconnected-(U1-R{slash}PIO0_11{slash}AD0{slash}CT32B0_MAT3-Pad32)") (class "Default")
      (node (ref "U1") (pin "32") (pinfunction "R/PIO0_11/AD0/CT32B0_MAT3_32") (pintype "bidirectional"))
    )
    (net (code "142") (name "unconnected-(U1-R{slash}PIO1_0{slash}AD1{slash}CT32B1_CAP0-Pad33)") (class "Default")
      (node (ref "U1") (pin "33") (pinfunction "R/PIO1_0/AD1/CT32B1_CAP0_33") (pintype "bidirectional"))
    )
    (net (code "143") (name "unconnected-(U1-R{slash}PIO1_1{slash}AD2{slash}CT32B1_MAT0-Pad34)") (class "Default")
      (node (ref "U1") (pin "34") (pinfunction "R/PIO1_1/AD2/CT32B1_MAT0_34") (pintype "bidirectional"))
    )
    (net (code "144") (name "unconnected-(U1-R{slash}PIO1_2{slash}AD3{slash}CT32B1_MAT1-Pad35)") (class "Default")
      (node (ref "U1") (pin "35") (pinfunction "R/PIO1_2/AD3/CT32B1_MAT1_35") (pintype "bidirectional"))
    )
    (net (code "145") (name "unconnected-(X1-Pad4)") (class "Default")
      (node (ref "X1") (pin "4") (pinfunction "4_4") (pintype "passive"))
    )
    (net (code "146") (name "unconnected-(X2-Pad31)") (class "Default")
      (node (ref "X2") (pin "31") (pinfunction "31_31") (pintype "passive"))
    )
    (net (code "147") (name "unconnected-(X2-Pad35)") (class "Default")
      (node (ref "X2") (pin "35") (pinfunction "35_35") (pintype "passive"))
    )
    (net (code "148") (name "unconnected-(X2-Pad37)") (class "Default")
      (node (ref "X2") (pin "37") (pinfunction "37_37") (pintype "passive"))
    )
    (net (code "149") (name "unconnected-(X2-Pad38)") (class "Default")
      (node (ref "X2") (pin "38") (pinfunction "38_38") (pintype "passive"))
    )
    (net (code "150") (name "unconnected-(X2-Pad39)") (class "Default")
      (node (ref "X2") (pin "39") (pinfunction "39_39") (pintype "passive"))
    )
    (net (code "151") (name "unconnected-(X2-Pad40)") (class "Default")
      (node (ref "X2") (pin "40") (pinfunction "40_40") (pintype "passive"))
    )
  )
)
